# teensy_speeduino_5_1.net
KiCad netlist of a schematic drawn in EAGLE
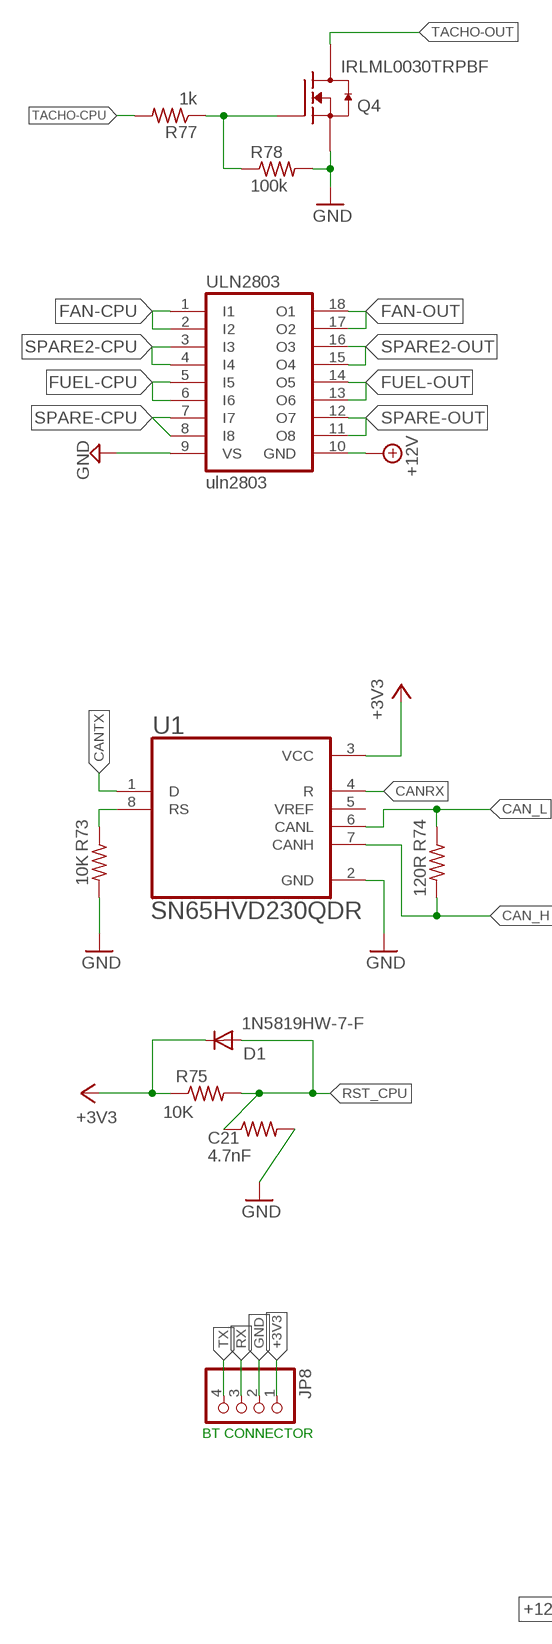
[diagram p0: schematic, sheet 1, part 1 of 2]
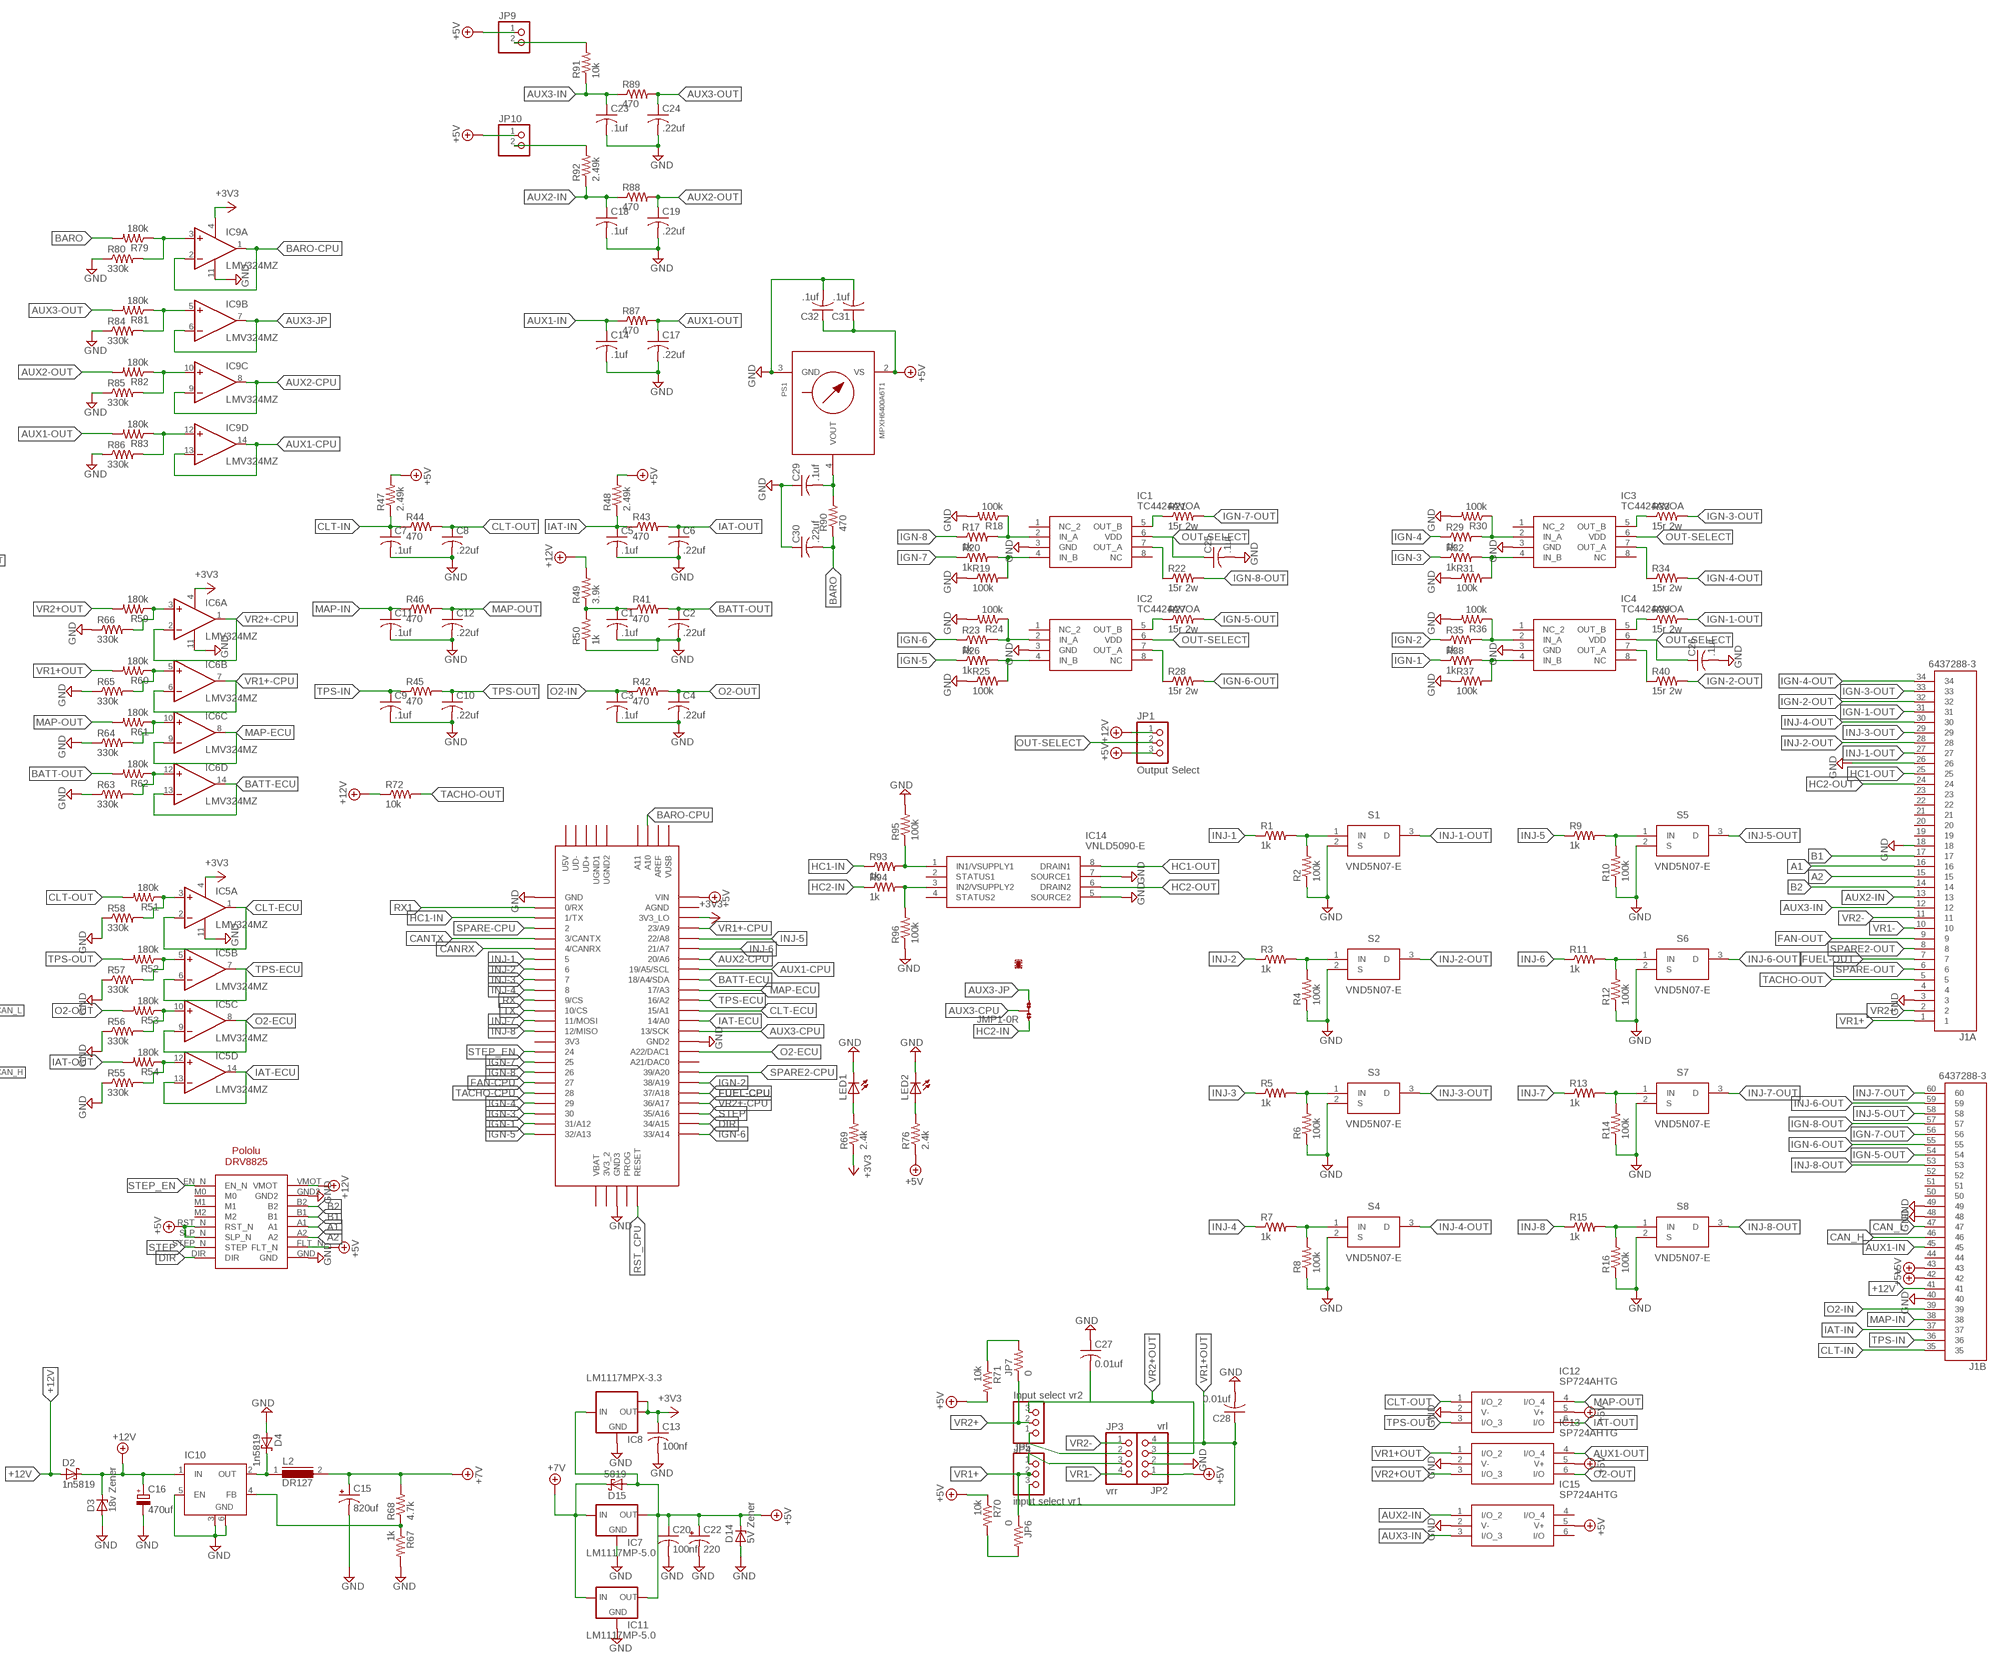
[diagram p1: schematic, sheet 1, part 2 of 2]

(export (version "E")
  (design (tool "Eeschema 10.0.6"))
  (components
    (comp (ref "C1")
      (value ".1uf")
      (footprint "eagle-import:C1206")
      (libsource (lib "eagle-import") (part "C-USC1206"))
    )
    (comp (ref "C2")
      (value ".22uf")
      (footprint "eagle-import:C1206")
      (libsource (lib "eagle-import") (part "C-USC1206"))
    )
    (comp (ref "C3")
      (value ".1uf")
      (footprint "eagle-import:C1206")
      (libsource (lib "eagle-import") (part "C-USC1206"))
    )
    (comp (ref "C4")
      (value ".22uf")
      (footprint "eagle-import:C1206")
      (libsource (lib "eagle-import") (part "C-USC1206"))
    )
    (comp (ref "C5")
      (value ".1uf")
      (footprint "eagle-import:C1206")
      (libsource (lib "eagle-import") (part "C-USC1206"))
    )
    (comp (ref "C6")
      (value ".22uf")
      (footprint "eagle-import:C1206")
      (libsource (lib "eagle-import") (part "C-USC1206"))
    )
    (comp (ref "C7")
      (value ".1uf")
      (footprint "eagle-import:C1206")
      (libsource (lib "eagle-import") (part "C-USC1206"))
    )
    (comp (ref "C8")
      (value ".22uf")
      (footprint "eagle-import:C1206")
      (libsource (lib "eagle-import") (part "C-USC1206"))
    )
    (comp (ref "C9")
      (value ".1uf")
      (footprint "eagle-import:C1206")
      (libsource (lib "eagle-import") (part "C-USC1206"))
    )
    (comp (ref "C10")
      (value ".22uf")
      (footprint "eagle-import:C1206")
      (libsource (lib "eagle-import") (part "C-USC1206"))
    )
    (comp (ref "C11")
      (value ".1uf")
      (footprint "eagle-import:C1206")
      (libsource (lib "eagle-import") (part "C-USC1206"))
    )
    (comp (ref "C12")
      (value ".22uf")
      (footprint "eagle-import:C1206")
      (libsource (lib "eagle-import") (part "C-USC1206"))
    )
    (comp (ref "C13")
      (value "100nf")
      (footprint "eagle-import:C1206")
      (libsource (lib "eagle-import") (part "C-USC1206"))
    )
    (comp (ref "C14")
      (value ".1uf")
      (footprint "eagle-import:C0805")
      (libsource (lib "eagle-import") (part "C-USC0805"))
    )
    (comp (ref "C15")
      (value "820uf")
      (footprint "eagle-import:153CLV-0810")
      (libsource (lib "eagle-import") (part "CPOL-US153CLV-0810"))
    )
    (comp (ref "C16")
      (value "470uf")
      (footprint "eagle-import:153CLV-0810")
      (libsource (lib "eagle-import") (part "CPOL-EU153CLV-0810"))
    )
    (comp (ref "C17")
      (value ".22uf")
      (footprint "eagle-import:C0805")
      (libsource (lib "eagle-import") (part "C-USC0805"))
    )
    (comp (ref "C18")
      (value ".1uf")
      (footprint "eagle-import:C0805")
      (libsource (lib "eagle-import") (part "C-USC0805"))
    )
    (comp (ref "C19")
      (value ".22uf")
      (footprint "eagle-import:C0805")
      (libsource (lib "eagle-import") (part "C-USC0805"))
    )
    (comp (ref "C20")
      (value "100nf")
      (footprint "eagle-import:C1206")
      (libsource (lib "eagle-import") (part "C-USC1206"))
    )
    (comp (ref "C21")
      (value "4.7nF")
      (footprint "eagle-import:R1206")
      (libsource (lib "eagle-import") (part "R-US_R1206"))
    )
    (comp (ref "C22")
      (value "220")
      (footprint "eagle-import:153CLV-0605")
      (libsource (lib "eagle-import") (part "CPOL-US153CLV-0605"))
    )
    (comp (ref "C23")
      (value ".1uf")
      (footprint "eagle-import:C0805")
      (libsource (lib "eagle-import") (part "C-USC0805"))
    )
    (comp (ref "C24")
      (value ".22uf")
      (footprint "eagle-import:C0805")
      (libsource (lib "eagle-import") (part "C-USC0805"))
    )
    (comp (ref "C25")
      (value ".1uf")
      (footprint "eagle-import:C0805")
      (libsource (lib "eagle-import") (part "C-USC0805"))
    )
    (comp (ref "C26")
      (value ".1uf")
      (footprint "eagle-import:C0805")
      (libsource (lib "eagle-import") (part "C-USC0805"))
    )
    (comp (ref "C27")
      (value "0.01uf")
      (footprint "eagle-import:C1206")
      (libsource (lib "eagle-import") (part "C-USC1206"))
    )
    (comp (ref "C28")
      (value "0.01uf")
      (footprint "eagle-import:C1206")
      (libsource (lib "eagle-import") (part "C-USC1206"))
    )
    (comp (ref "C29")
      (value ".1uf")
      (footprint "eagle-import:C1206")
      (libsource (lib "eagle-import") (part "C-USC1206"))
    )
    (comp (ref "C30")
      (value ".22uf")
      (footprint "eagle-import:C1206")
      (libsource (lib "eagle-import") (part "C-USC1206"))
    )
    (comp (ref "C31")
      (value ".1uf")
      (footprint "eagle-import:C1206")
      (libsource (lib "eagle-import") (part "C-USC1206"))
    )
    (comp (ref "C32")
      (value ".1uf")
      (footprint "eagle-import:C1206")
      (libsource (lib "eagle-import") (part "C-USC1206"))
    )
    (comp (ref "D1")
      (value "1N5819HW-7-F")
      (footprint "eagle-import:SOD123")
      (libsource (lib "eagle-import") (part "DIODE-SOD123"))
    )
    (comp (ref "D2")
      (value "1n5819")
      (footprint "eagle-import:SMB")
      (libsource (lib "eagle-import") (part "SCHOTTKY-DIODESMD"))
    )
    (comp (ref "D3")
      (value "18v Zener")
      (footprint "eagle-import:SMB")
      (libsource (lib "eagle-import") (part "ZENER-DIODESMB"))
    )
    (comp (ref "D4")
      (value "1n5819")
      (footprint "eagle-import:SMB")
      (libsource (lib "eagle-import") (part "SCHOTTKY-DIODESMD"))
    )
    (comp (ref "D14")
      (value "5V Zener")
      (footprint "eagle-import:SMB")
      (libsource (lib "eagle-import") (part "ZENER-DIODESMB"))
    )
    (comp (ref "D15")
      (value "5819")
      (footprint "eagle-import:SMB")
      (libsource (lib "eagle-import") (part "SCHOTTKY-DIODESMD"))
    )
    (comp (ref "IC1")
      (value "TC4424AVOA")
      (footprint "eagle-import:SOIC127P600X175-8N")
      (libsource (lib "eagle-import") (part "TC4424AVOA"))
    )
    (comp (ref "IC2")
      (value "TC4424AVOA")
      (footprint "eagle-import:SOIC127P600X175-8N")
      (libsource (lib "eagle-import") (part "TC4424AVOA"))
    )
    (comp (ref "IC3")
      (value "TC4424AVOA")
      (footprint "eagle-import:SOIC127P600X175-8N")
      (libsource (lib "eagle-import") (part "TC4424AVOA"))
    )
    (comp (ref "IC4")
      (value "TC4424AVOA")
      (footprint "eagle-import:SOIC127P600X175-8N")
      (libsource (lib "eagle-import") (part "TC4424AVOA"))
    )
    (comp (ref "IC5")
      (value "LMV324MZ")
      (footprint "eagle-import:TSSOP14")
      (libsource (lib "eagle-import") (part "LMV324?MZ"))
    )
    (comp (ref "IC6")
      (value "LMV324MZ")
      (footprint "eagle-import:TSSOP14")
      (libsource (lib "eagle-import") (part "LMV324?MZ"))
    )
    (comp (ref "IC7")
      (value "LM1117MP-5.0")
      (footprint "eagle-import:SOT223")
      (fields (field (name "MF") "Texas Instruments"))
      (libsource (lib "eagle-import") (part "LM1117?-MP5.0"))
    )
    (comp (ref "IC8")
      (value "LM1117MPX-3.3")
      (footprint "eagle-import:SOT223")
      (libsource (lib "eagle-import") (part "LM1117MPX-3.3"))
    )
    (comp (ref "IC9")
      (value "LMV324MZ")
      (footprint "eagle-import:TSSOP14")
      (libsource (lib "eagle-import") (part "LMV324?MZ"))
    )
    (comp (ref "IC10")
      (value "LM2596S")
      (footprint "eagle-import:TO263-5")
      (libsource (lib "eagle-import") (part "LM2596S"))
    )
    (comp (ref "IC11")
      (value "LM1117MP-5.0")
      (footprint "eagle-import:SOT223")
      (fields (field (name "MF") "Texas Instruments"))
      (libsource (lib "eagle-import") (part "LM1117?-MP5.0"))
    )
    (comp (ref "IC12")
      (value "SP724AHTG")
      (footprint "eagle-import:SOT95P280X145-6N")
      (fields (field (name "RS_PART_NUMBER") "7931982"))
      (libsource (lib "eagle-import") (part "SP724AHTG"))
    )
    (comp (ref "IC13")
      (value "SP724AHTG")
      (footprint "eagle-import:SOT95P280X145-6N")
      (fields (field (name "RS_PART_NUMBER") "7931982"))
      (libsource (lib "eagle-import") (part "SP724AHTG"))
    )
    (comp (ref "IC14")
      (value "VNLD5090-E")
      (footprint "eagle-import:SOIC127P600X175-8N")
      (fields (field (name "MOUSER_PART_NUMBER") "511-VNLD5090-E"))
      (libsource (lib "eagle-import") (part "VNLD5090-E"))
    )
    (comp (ref "IC15")
      (value "SP724AHTG")
      (footprint "eagle-import:SOT95P280X145-6N")
      (fields (field (name "RS_PART_NUMBER") "7931982"))
      (libsource (lib "eagle-import") (part "SP724AHTG"))
    )
    (comp (ref "J1")
      (value "6437288-3")
      (footprint "eagle-import:TE_6437288-3")
      (fields (field (name "DIGI-KEY_PART_NUMBER") "A122211-ND") (field (name "MF") "TE Connectivity"))
      (libsource (lib "eagle-import") (part "6437288-3"))
    )
    (comp (ref "JMP1")
      (value "0R-JUMPA")
      (footprint "eagle-import:A0R-JMP")
      (libsource (lib "eagle-import") (part "0R-JUMPA"))
    )
    (comp (ref "JP1")
      (value "Output Select")
      (footprint "eagle-import:1X03")
      (libsource (lib "eagle-import") (part "PINHD-1X3"))
    )
    (comp (ref "JP2")
      (value "vrl")
      (footprint "eagle-import:1X04")
      (libsource (lib "eagle-import") (part "pinhead_325_PINHD-1X4"))
    )
    (comp (ref "JP3")
      (value "vrr")
      (footprint "eagle-import:1X04")
      (libsource (lib "eagle-import") (part "pinhead_325_PINHD-1X4"))
    )
    (comp (ref "JP4")
      (value "Input select vr2")
      (footprint "eagle-import:1X03")
      (libsource (lib "eagle-import") (part "PINHD-1X3"))
    )
    (comp (ref "JP5")
      (value "input select vr1")
      (footprint "eagle-import:1X03")
      (libsource (lib "eagle-import") (part "PINHD-1X3"))
    )
    (comp (ref "JP6")
      (value "0")
      (footprint "eagle-import:R0805")
      (libsource (lib "eagle-import") (part "R-US_R0805"))
    )
    (comp (ref "JP7")
      (value "0")
      (footprint "eagle-import:R0805")
      (libsource (lib "eagle-import") (part "R-US_R0805"))
    )
    (comp (ref "JP8")
      (value "PINHD-1X4")
      (footprint "eagle-import:1X04")
      (libsource (lib "eagle-import") (part "PINHD-1X4"))
    )
    (comp (ref "JP9")
      (value "PINHD-1X2")
      (footprint "eagle-import:1X02")
      (libsource (lib "eagle-import") (part "PINHD-1X2"))
    )
    (comp (ref "JP10")
      (value "PINHD-1X2")
      (footprint "eagle-import:1X02")
      (libsource (lib "eagle-import") (part "PINHD-1X2"))
    )
    (comp (ref "L2")
      (value "DR127")
      (footprint "eagle-import:DR127")
      (libsource (lib "eagle-import") (part "DR127"))
    )
    (comp (ref "LED1")
      (value "LEDSML1206")
      (footprint "eagle-import:SML1206")
      (libsource (lib "eagle-import") (part "LEDSML1206"))
    )
    (comp (ref "LED2")
      (value "LEDSML1206")
      (footprint "eagle-import:SML1206")
      (libsource (lib "eagle-import") (part "LEDSML1206"))
    )
    (comp (ref "PS1")
      (value "MPXH6400A6T1")
      (footprint "eagle-import:1317")
      (libsource (lib "eagle-import") (part "MPXH6400A6T1"))
    )
    (comp (ref "Q4")
      (value "IRLML0030TRPBF")
      (footprint "eagle-import:SOT95P280X135-3N")
      (libsource (lib "eagle-import") (part "MOSFET-NCH_SOT-23"))
    )
    (comp (ref "R1")
      (value "1k")
      (footprint "eagle-import:R1206")
      (libsource (lib "eagle-import") (part "R-US_R1206"))
    )
    (comp (ref "R2")
      (value "100k")
      (footprint "eagle-import:R1206")
      (libsource (lib "eagle-import") (part "R-US_R1206"))
    )
    (comp (ref "R3")
      (value "1k")
      (footprint "eagle-import:R1206")
      (libsource (lib "eagle-import") (part "R-US_R1206"))
    )
    (comp (ref "R4")
      (value "100k")
      (footprint "eagle-import:R1206")
      (libsource (lib "eagle-import") (part "R-US_R1206"))
    )
    (comp (ref "R5")
      (value "1k")
      (footprint "eagle-import:R1206")
      (libsource (lib "eagle-import") (part "R-US_R1206"))
    )
    (comp (ref "R6")
      (value "100k")
      (footprint "eagle-import:R1206")
      (libsource (lib "eagle-import") (part "R-US_R1206"))
    )
    (comp (ref "R7")
      (value "1k")
      (footprint "eagle-import:R1206")
      (libsource (lib "eagle-import") (part "R-US_R1206"))
    )
    (comp (ref "R8")
      (value "100k")
      (footprint "eagle-import:R1206")
      (libsource (lib "eagle-import") (part "R-US_R1206"))
    )
    (comp (ref "R9")
      (value "1k")
      (footprint "eagle-import:R1206")
      (libsource (lib "eagle-import") (part "R-US_R1206"))
    )
    (comp (ref "R10")
      (value "100k")
      (footprint "eagle-import:R1206")
      (libsource (lib "eagle-import") (part "R-US_R1206"))
    )
    (comp (ref "R11")
      (value "1k")
      (footprint "eagle-import:R1206")
      (libsource (lib "eagle-import") (part "R-US_R1206"))
    )
    (comp (ref "R12")
      (value "100k")
      (footprint "eagle-import:R1206")
      (libsource (lib "eagle-import") (part "R-US_R1206"))
    )
    (comp (ref "R13")
      (value "1k")
      (footprint "eagle-import:R1206")
      (libsource (lib "eagle-import") (part "R-US_R1206"))
    )
    (comp (ref "R14")
      (value "100k")
      (footprint "eagle-import:R1206")
      (libsource (lib "eagle-import") (part "R-US_R1206"))
    )
    (comp (ref "R15")
      (value "1k")
      (footprint "eagle-import:R1206")
      (libsource (lib "eagle-import") (part "R-US_R1206"))
    )
    (comp (ref "R16")
      (value "100k")
      (footprint "eagle-import:R1206")
      (libsource (lib "eagle-import") (part "R-US_R1206"))
    )
    (comp (ref "R17")
      (value "1k")
      (footprint "eagle-import:R1206")
      (libsource (lib "eagle-import") (part "R-US_R1206"))
    )
    (comp (ref "R18")
      (value "100k")
      (footprint "eagle-import:R1206")
      (libsource (lib "eagle-import") (part "R-US_R1206"))
    )
    (comp (ref "R19")
      (value "100k")
      (footprint "eagle-import:R1206")
      (libsource (lib "eagle-import") (part "R-US_R1206"))
    )
    (comp (ref "R20")
      (value "1k")
      (footprint "eagle-import:R1206")
      (libsource (lib "eagle-import") (part "R-US_R1206"))
    )
    (comp (ref "R21")
      (value "15r 2w")
      (footprint "eagle-import:R2512")
      (libsource (lib "eagle-import") (part "R-US_R2512"))
    )
    (comp (ref "R22")
      (value "15r 2w")
      (footprint "eagle-import:R2512")
      (libsource (lib "eagle-import") (part "R-US_R2512"))
    )
    (comp (ref "R23")
      (value "1k")
      (footprint "eagle-import:R1206")
      (libsource (lib "eagle-import") (part "R-US_R1206"))
    )
    (comp (ref "R24")
      (value "100k")
      (footprint "eagle-import:R1206")
      (libsource (lib "eagle-import") (part "R-US_R1206"))
    )
    (comp (ref "R25")
      (value "100k")
      (footprint "eagle-import:R1206")
      (libsource (lib "eagle-import") (part "R-US_R1206"))
    )
    (comp (ref "R26")
      (value "1k")
      (footprint "eagle-import:R1206")
      (libsource (lib "eagle-import") (part "R-US_R1206"))
    )
    (comp (ref "R27")
      (value "15r 2w")
      (footprint "eagle-import:R2512")
      (libsource (lib "eagle-import") (part "R-US_R2512"))
    )
    (comp (ref "R28")
      (value "15r 2w")
      (footprint "eagle-import:R2512")
      (libsource (lib "eagle-import") (part "R-US_R2512"))
    )
    (comp (ref "R29")
      (value "1k")
      (footprint "eagle-import:R1206")
      (libsource (lib "eagle-import") (part "R-US_R1206"))
    )
    (comp (ref "R30")
      (value "100k")
      (footprint "eagle-import:R1206")
      (libsource (lib "eagle-import") (part "R-US_R1206"))
    )
    (comp (ref "R31")
      (value "100k")
      (footprint "eagle-import:R1206")
      (libsource (lib "eagle-import") (part "R-US_R1206"))
    )
    (comp (ref "R32")
      (value "1k")
      (footprint "eagle-import:R1206")
      (libsource (lib "eagle-import") (part "R-US_R1206"))
    )
    (comp (ref "R33")
      (value "15r 2w")
      (footprint "eagle-import:R2512")
      (libsource (lib "eagle-import") (part "R-US_R2512"))
    )
    (comp (ref "R34")
      (value "15r 2w")
      (footprint "eagle-import:R2512")
      (libsource (lib "eagle-import") (part "R-US_R2512"))
    )
    (comp (ref "R35")
      (value "1k")
      (footprint "eagle-import:R1206")
      (libsource (lib "eagle-import") (part "R-US_R1206"))
    )
    (comp (ref "R36")
      (value "100k")
      (footprint "eagle-import:R1206")
      (libsource (lib "eagle-import") (part "R-US_R1206"))
    )
    (comp (ref "R37")
      (value "100k")
      (footprint "eagle-import:R1206")
      (libsource (lib "eagle-import") (part "R-US_R1206"))
    )
    (comp (ref "R38")
      (value "1k")
      (footprint "eagle-import:R1206")
      (libsource (lib "eagle-import") (part "R-US_R1206"))
    )
    (comp (ref "R39")
      (value "15r 2w")
      (footprint "eagle-import:R2512")
      (libsource (lib "eagle-import") (part "R-US_R2512"))
    )
    (comp (ref "R40")
      (value "15r 2w")
      (footprint "eagle-import:R2512")
      (libsource (lib "eagle-import") (part "R-US_R2512"))
    )
    (comp (ref "R41")
      (value "470")
      (footprint "eagle-import:R1206")
      (libsource (lib "eagle-import") (part "R-US_R1206"))
    )
    (comp (ref "R42")
      (value "470")
      (footprint "eagle-import:R1206")
      (libsource (lib "eagle-import") (part "R-US_R1206"))
    )
    (comp (ref "R43")
      (value "470")
      (footprint "eagle-import:R1206")
      (libsource (lib "eagle-import") (part "R-US_R1206"))
    )
    (comp (ref "R44")
      (value "470")
      (footprint "eagle-import:R1206")
      (libsource (lib "eagle-import") (part "R-US_R1206"))
    )
    (comp (ref "R45")
      (value "470")
      (footprint "eagle-import:R1206")
      (libsource (lib "eagle-import") (part "R-US_R1206"))
    )
    (comp (ref "R46")
      (value "470")
      (footprint "eagle-import:R1206")
      (libsource (lib "eagle-import") (part "R-US_R1206"))
    )
    (comp (ref "R47")
      (value "2.49k")
      (footprint "eagle-import:R1206")
      (libsource (lib "eagle-import") (part "R-US_R1206"))
    )
    (comp (ref "R48")
      (value "2.49k")
      (footprint "eagle-import:R1206")
      (libsource (lib "eagle-import") (part "R-US_R1206"))
    )
    (comp (ref "R49")
      (value "3.9k")
      (footprint "eagle-import:R1206")
      (libsource (lib "eagle-import") (part "R-US_R1206"))
    )
    (comp (ref "R50")
      (value "1k")
      (footprint "eagle-import:R1206")
      (libsource (lib "eagle-import") (part "R-US_R1206"))
    )
    (comp (ref "R51")
      (value "180k")
      (footprint "eagle-import:R1206")
      (libsource (lib "eagle-import") (part "R-US_R1206"))
    )
    (comp (ref "R52")
      (value "180k")
      (footprint "eagle-import:R1206")
      (libsource (lib "eagle-import") (part "R-US_R1206"))
    )
    (comp (ref "R53")
      (value "180k")
      (footprint "eagle-import:R1206")
      (libsource (lib "eagle-import") (part "R-US_R1206"))
    )
    (comp (ref "R54")
      (value "180k")
      (footprint "eagle-import:R1206")
      (libsource (lib "eagle-import") (part "R-US_R1206"))
    )
    (comp (ref "R55")
      (value "330k")
      (footprint "eagle-import:R1206")
      (libsource (lib "eagle-import") (part "R-US_R1206"))
    )
    (comp (ref "R56")
      (value "330k")
      (footprint "eagle-import:R1206")
      (libsource (lib "eagle-import") (part "R-US_R1206"))
    )
    (comp (ref "R57")
      (value "330k")
      (footprint "eagle-import:R1206")
      (libsource (lib "eagle-import") (part "R-US_R1206"))
    )
    (comp (ref "R58")
      (value "330k")
      (footprint "eagle-import:R1206")
      (libsource (lib "eagle-import") (part "R-US_R1206"))
    )
    (comp (ref "R59")
      (value "180k")
      (footprint "eagle-import:R1206")
      (libsource (lib "eagle-import") (part "R-US_R1206"))
    )
    (comp (ref "R60")
      (value "180k")
      (footprint "eagle-import:R1206")
      (libsource (lib "eagle-import") (part "R-US_R1206"))
    )
    (comp (ref "R61")
      (value "180k")
      (footprint "eagle-import:R1206")
      (libsource (lib "eagle-import") (part "R-US_R1206"))
    )
    (comp (ref "R62")
      (value "180k")
      (footprint "eagle-import:R1206")
      (libsource (lib "eagle-import") (part "R-US_R1206"))
    )
    (comp (ref "R63")
      (value "330k")
      (footprint "eagle-import:R1206")
      (libsource (lib "eagle-import") (part "R-US_R1206"))
    )
    (comp (ref "R64")
      (value "330k")
      (footprint "eagle-import:R1206")
      (libsource (lib "eagle-import") (part "R-US_R1206"))
    )
    (comp (ref "R65")
      (value "330k")
      (footprint "eagle-import:R1206")
      (libsource (lib "eagle-import") (part "R-US_R1206"))
    )
    (comp (ref "R66")
      (value "330k")
      (footprint "eagle-import:R1206")
      (libsource (lib "eagle-import") (part "R-US_R1206"))
    )
    (comp (ref "R67")
      (value "1k")
      (footprint "eagle-import:R1206")
      (libsource (lib "eagle-import") (part "R-US_R1206"))
    )
    (comp (ref "R68")
      (value "4.7k")
      (footprint "eagle-import:R1206")
      (libsource (lib "eagle-import") (part "R-US_R1206"))
    )
    (comp (ref "R69")
      (value "2.4k")
      (footprint "eagle-import:R1206")
      (libsource (lib "eagle-import") (part "R-US_R1206"))
    )
    (comp (ref "R70")
      (value "10k")
      (footprint "eagle-import:R1206")
      (libsource (lib "eagle-import") (part "R-US_R1206"))
    )
    (comp (ref "R71")
      (value "10k")
      (footprint "eagle-import:R1206")
      (libsource (lib "eagle-import") (part "R-US_R1206"))
    )
    (comp (ref "R72")
      (value "10k")
      (footprint "eagle-import:R1206")
      (libsource (lib "eagle-import") (part "R-US_R1206"))
    )
    (comp (ref "R73")
      (value "10K")
      (footprint "eagle-import:R1206")
      (libsource (lib "eagle-import") (part "R-US_R1206"))
    )
    (comp (ref "R74")
      (value "120R")
      (footprint "eagle-import:R1206")
      (libsource (lib "eagle-import") (part "R-US_R1206"))
    )
    (comp (ref "R75")
      (value "10K")
      (footprint "eagle-import:R1206")
      (libsource (lib "eagle-import") (part "R-US_R1206"))
    )
    (comp (ref "R76")
      (value "2.4k")
      (footprint "eagle-import:R1206")
      (libsource (lib "eagle-import") (part "R-US_R1206"))
    )
    (comp (ref "R77")
      (value "1k")
      (footprint "eagle-import:R1206")
      (libsource (lib "eagle-import") (part "R-US_R1206"))
    )
    (comp (ref "R78")
      (value "100k")
      (footprint "eagle-import:R1206")
      (libsource (lib "eagle-import") (part "R-US_R1206"))
    )
    (comp (ref "R79")
      (value "180k")
      (footprint "eagle-import:R0805")
      (libsource (lib "eagle-import") (part "R-US_R0805"))
    )
    (comp (ref "R80")
      (value "330k")
      (footprint "eagle-import:R0805")
      (libsource (lib "eagle-import") (part "R-US_R0805"))
    )
    (comp (ref "R81")
      (value "180k")
      (footprint "eagle-import:R0805")
      (libsource (lib "eagle-import") (part "R-US_R0805"))
    )
    (comp (ref "R82")
      (value "180k")
      (footprint "eagle-import:R0805")
      (libsource (lib "eagle-import") (part "R-US_R0805"))
    )
    (comp (ref "R83")
      (value "180k")
      (footprint "eagle-import:R0805")
      (libsource (lib "eagle-import") (part "R-US_R0805"))
    )
    (comp (ref "R84")
      (value "330k")
      (footprint "eagle-import:R0805")
      (libsource (lib "eagle-import") (part "R-US_R0805"))
    )
    (comp (ref "R85")
      (value "330k")
      (footprint "eagle-import:R0805")
      (libsource (lib "eagle-import") (part "R-US_R0805"))
    )
    (comp (ref "R86")
      (value "330k")
      (footprint "eagle-import:R0805")
      (libsource (lib "eagle-import") (part "R-US_R0805"))
    )
    (comp (ref "R87")
      (value "470")
      (footprint "eagle-import:R0805")
      (libsource (lib "eagle-import") (part "R-US_R0805"))
    )
    (comp (ref "R88")
      (value "470")
      (footprint "eagle-import:R0805")
      (libsource (lib "eagle-import") (part "R-US_R0805"))
    )
    (comp (ref "R89")
      (value "470")
      (footprint "eagle-import:R0805")
      (libsource (lib "eagle-import") (part "R-US_R0805"))
    )
    (comp (ref "R90")
      (value "470")
      (footprint "eagle-import:R1206")
      (libsource (lib "eagle-import") (part "R-US_R1206"))
    )
    (comp (ref "R91")
      (value "10k")
      (footprint "eagle-import:R1206")
      (libsource (lib "eagle-import") (part "R-US_R1206"))
    )
    (comp (ref "R92")
      (value "2.49k")
      (footprint "eagle-import:R1206")
      (libsource (lib "eagle-import") (part "R-US_R1206"))
    )
    (comp (ref "R93")
      (value "1k")
      (footprint "eagle-import:R1206")
      (libsource (lib "eagle-import") (part "R-US_R1206"))
    )
    (comp (ref "R94")
      (value "1k")
      (footprint "eagle-import:R1206")
      (libsource (lib "eagle-import") (part "R-US_R1206"))
    )
    (comp (ref "R95")
      (value "100k")
      (footprint "eagle-import:R1206")
      (libsource (lib "eagle-import") (part "R-US_R1206"))
    )
    (comp (ref "R96")
      (value "100k")
      (footprint "eagle-import:R1206")
      (libsource (lib "eagle-import") (part "R-US_R1206"))
    )
    (comp (ref "S1")
      (value "VND5N07-E")
      (footprint "eagle-import:TO-252-(DPAK)_1")
      (fields (field (name "RS_PART_NUMBER") "3511351"))
      (libsource (lib "eagle-import") (part "VND5N07-E"))
    )
    (comp (ref "S2")
      (value "VND5N07-E")
      (footprint "eagle-import:TO-252-(DPAK)_1")
      (fields (field (name "RS_PART_NUMBER") "3511351"))
      (libsource (lib "eagle-import") (part "VND5N07-E"))
    )
    (comp (ref "S3")
      (value "VND5N07-E")
      (footprint "eagle-import:TO-252-(DPAK)_1")
      (fields (field (name "RS_PART_NUMBER") "3511351"))
      (libsource (lib "eagle-import") (part "VND5N07-E"))
    )
    (comp (ref "S4")
      (value "VND5N07-E")
      (footprint "eagle-import:TO-252-(DPAK)_1")
      (fields (field (name "RS_PART_NUMBER") "3511351"))
      (libsource (lib "eagle-import") (part "VND5N07-E"))
    )
    (comp (ref "S5")
      (value "VND5N07-E")
      (footprint "eagle-import:TO-252-(DPAK)_1")
      (fields (field (name "RS_PART_NUMBER") "3511351"))
      (libsource (lib "eagle-import") (part "VND5N07-E"))
    )
    (comp (ref "S6")
      (value "VND5N07-E")
      (footprint "eagle-import:TO-252-(DPAK)_1")
      (fields (field (name "RS_PART_NUMBER") "3511351"))
      (libsource (lib "eagle-import") (part "VND5N07-E"))
    )
    (comp (ref "S7")
      (value "VND5N07-E")
      (footprint "eagle-import:TO-252-(DPAK)_1")
      (fields (field (name "RS_PART_NUMBER") "3511351"))
      (libsource (lib "eagle-import") (part "VND5N07-E"))
    )
    (comp (ref "S8")
      (value "VND5N07-E")
      (footprint "eagle-import:TO-252-(DPAK)_1")
      (fields (field (name "RS_PART_NUMBER") "3511351"))
      (libsource (lib "eagle-import") (part "VND5N07-E"))
    )
    (comp (ref "U$1")
      (value "TEENSY_3.5/3.6")
      (footprint "eagle-import:TEENSY_3.5_3.6")
      (libsource (lib "eagle-import") (part "TEENSY_3.5/3.6"))
    )
    (comp (ref "U$3")
      (value "POLOLU-DRV8825")
      (footprint "eagle-import:POLOLU-DRV8825")
      (libsource (lib "eagle-import") (part "POLOLU-DRV8825"))
    )
    (comp (ref "U1")
      (value "SN65HVD230QDR")
      (footprint "eagle-import:SOIC127P600X175-8N")
      (fields (field (name "MF") "Texas Instruments"))
      (libsource (lib "eagle-import") (part "SN65HVD230QDR"))
    )
    (comp (ref "ULN2803")
      (value "uln2803")
      (footprint "eagle-import:SO18W")
      (libsource (lib "eagle-import") (part "UDN298LW4"))
    )
  )
  (nets
    (net (code "1") (name "+3V3") (class "Default")
      (node (ref "C13") (pin "1") (pinfunction "1_1") (pintype "passive"))
      (node (ref "D1") (pin "C") (pinfunction "C_C") (pintype "passive"))
      (node (ref "IC5") (pin "4") (pinfunction "V+_4") (pintype "power_in"))
      (node (ref "IC6") (pin "4") (pinfunction "V+_4") (pintype "power_in"))
      (node (ref "IC8") (pin "2") (pinfunction "OUT_2") (pintype "passive"))
      (node (ref "IC8") (pin "TAB") (pinfunction "OUT1_TAB") (pintype "passive"))
      (node (ref "IC9") (pin "4") (pinfunction "V+_4") (pintype "power_in"))
      (node (ref "JP8") (pin "1") (pinfunction "1_1") (pintype "passive"))
      (node (ref "R69") (pin "1") (pinfunction "1_1") (pintype "passive"))
      (node (ref "R75") (pin "1") (pinfunction "1_1") (pintype "passive"))
      (node (ref "U$1") (pin "3V3_LO") (pinfunction "3V3_LO_3V3_LO") (pintype "bidirectional"))
      (node (ref "U1") (pin "3") (pinfunction "VCC_3") (pintype "power_in"))
    )
    (net (code "2") (name "+5V") (class "Default")
      (node (ref "C20") (pin "1") (pinfunction "1_1") (pintype "passive"))
      (node (ref "C22") (pin "+") (pinfunction "+_+") (pintype "passive"))
      (node (ref "C31") (pin "1") (pinfunction "1_1") (pintype "passive"))
      (node (ref "C32") (pin "1") (pinfunction "1_1") (pintype "passive"))
      (node (ref "D14") (pin "C") (pinfunction "C_C") (pintype "passive"))
      (node (ref "D15") (pin "A") (pinfunction "A_A") (pintype "passive"))
      (node (ref "IC11") (pin "2") (pinfunction "OUT_2") (pintype "passive"))
      (node (ref "IC11") (pin "4") (pinfunction "OUT_4") (pintype "passive"))
      (node (ref "IC12") (pin "5") (pinfunction "V+_5") (pintype "bidirectional"))
      (node (ref "IC13") (pin "5") (pinfunction "V+_5") (pintype "bidirectional"))
      (node (ref "IC15") (pin "5") (pinfunction "V+_5") (pintype "bidirectional"))
      (node (ref "IC7") (pin "2") (pinfunction "OUT_2") (pintype "passive"))
      (node (ref "IC7") (pin "4") (pinfunction "OUT_4") (pintype "passive"))
      (node (ref "IC8") (pin "3") (pinfunction "IN_3") (pintype "input"))
      (node (ref "J1") (pin "42") (pinfunction "42_42") (pintype "passive"))
      (node (ref "J1") (pin "43") (pinfunction "43_43") (pintype "passive"))
      (node (ref "JP1") (pin "3") (pinfunction "3_3") (pintype "passive"))
      (node (ref "JP10") (pin "1") (pinfunction "1_1") (pintype "passive"))
      (node (ref "JP2") (pin "1") (pinfunction "1_1") (pintype "passive"))
      (node (ref "JP9") (pin "1") (pinfunction "1_1") (pintype "passive"))
      (node (ref "PS1") (pin "2") (pinfunction "VS_2") (pintype "power_in"))
      (node (ref "R47") (pin "2") (pinfunction "2_2") (pintype "passive"))
      (node (ref "R48") (pin "2") (pinfunction "2_2") (pintype "passive"))
      (node (ref "R70") (pin "1") (pinfunction "1_1") (pintype "passive"))
      (node (ref "R71") (pin "2") (pinfunction "2_2") (pintype "passive"))
      (node (ref "R76") (pin "1") (pinfunction "1_1") (pintype "passive"))
      (node (ref "U$1") (pin "VIN") (pinfunction "VIN_VIN") (pintype "bidirectional"))
      (node (ref "U$3") (pin "FLT_N") (pinfunction "FLT_N_FLT_N") (pintype "bidirectional"))
      (node (ref "U$3") (pin "RST_N") (pinfunction "RST_N_RST_N") (pintype "bidirectional"))
      (node (ref "U$3") (pin "SLP_N") (pinfunction "SLP_N_SLP_N") (pintype "bidirectional"))
    )
    (net (code "3") (name "+7V") (class "Default")
      (node (ref "C15") (pin "+") (pinfunction "+_+") (pintype "passive"))
      (node (ref "D15") (pin "C") (pinfunction "C_C") (pintype "passive"))
      (node (ref "IC11") (pin "3") (pinfunction "IN_3") (pintype "input"))
      (node (ref "IC7") (pin "3") (pinfunction "IN_3") (pintype "input"))
      (node (ref "L2") (pin "2") (pinfunction "2_2") (pintype "passive"))
      (node (ref "R68") (pin "2") (pinfunction "2_2") (pintype "passive"))
    )
    (net (code "4") (name "+12V") (class "Default")
      (node (ref "C16") (pin "+") (pinfunction "+_+") (pintype "passive"))
      (node (ref "D2") (pin "A") (pinfunction "A_A") (pintype "passive"))
      (node (ref "D2") (pin "C") (pinfunction "C_C") (pintype "passive"))
      (node (ref "D3") (pin "C") (pinfunction "C_C") (pintype "passive"))
      (node (ref "IC10") (pin "1") (pinfunction "IN_1") (pintype "input"))
      (node (ref "J1") (pin "41") (pinfunction "41_41") (pintype "passive"))
      (node (ref "JP1") (pin "1") (pinfunction "1_1") (pintype "passive"))
      (node (ref "R49") (pin "2") (pinfunction "2_2") (pintype "passive"))
      (node (ref "R72") (pin "1") (pinfunction "1_1") (pintype "passive"))
      (node (ref "U$3") (pin "VMOT") (pinfunction "VMOT_VMOT") (pintype "bidirectional"))
      (node (ref "ULN2803") (pin "10") (pinfunction "GND_10") (pintype "power_in"))
    )
    (net (code "5") (name "A1") (class "Default")
      (node (ref "J1") (pin "16") (pinfunction "16_16") (pintype "passive"))
      (node (ref "U$3") (pin "A1") (pinfunction "A1_A1") (pintype "bidirectional"))
    )
    (net (code "6") (name "A2") (class "Default")
      (node (ref "J1") (pin "15") (pinfunction "15_15") (pintype "passive"))
      (node (ref "U$3") (pin "A2") (pinfunction "A2_A2") (pintype "bidirectional"))
    )
    (net (code "7") (name "AUX1-CPU") (class "Default")
      (node (ref "IC9") (pin "13") (pinfunction "-IN_13") (pintype "input"))
      (node (ref "IC9") (pin "14") (pinfunction "OUT_14") (pintype "output"))
      (node (ref "U$1") (pin "19/A5/SCL") (pinfunction "19/A5/SCL_19/A5/SCL") (pintype "bidirectional"))
    )
    (net (code "8") (name "AUX1-IN") (class "Default")
      (node (ref "C14") (pin "1") (pinfunction "1_1") (pintype "passive"))
      (node (ref "J1") (pin "45") (pinfunction "45_45") (pintype "passive"))
      (node (ref "R87") (pin "1") (pinfunction "1_1") (pintype "passive"))
    )
    (net (code "9") (name "AUX1-OUT") (class "Default")
      (node (ref "C17") (pin "1") (pinfunction "1_1") (pintype "passive"))
      (node (ref "IC13") (pin "4") (pinfunction "I/O_4_4") (pintype "bidirectional"))
      (node (ref "R83") (pin "2") (pinfunction "2_2") (pintype "passive"))
      (node (ref "R87") (pin "2") (pinfunction "2_2") (pintype "passive"))
    )
    (net (code "10") (name "AUX2-CPU") (class "Default")
      (node (ref "IC9") (pin "8") (pinfunction "OUT_8") (pintype "output"))
      (node (ref "IC9") (pin "9") (pinfunction "-IN_9") (pintype "input"))
      (node (ref "U$1") (pin "20/A6") (pinfunction "20/A6_20/A6") (pintype "bidirectional"))
    )
    (net (code "11") (name "AUX2-IN") (class "Default")
      (node (ref "C18") (pin "1") (pinfunction "1_1") (pintype "passive"))
      (node (ref "IC15") (pin "1") (pinfunction "I/O_2_1") (pintype "bidirectional"))
      (node (ref "J1") (pin "13") (pinfunction "13_13") (pintype "passive"))
      (node (ref "R88") (pin "1") (pinfunction "1_1") (pintype "passive"))
      (node (ref "R92") (pin "1") (pinfunction "1_1") (pintype "passive"))
    )
    (net (code "12") (name "AUX2-OUT") (class "Default")
      (node (ref "C19") (pin "1") (pinfunction "1_1") (pintype "passive"))
      (node (ref "R82") (pin "2") (pinfunction "2_2") (pintype "passive"))
      (node (ref "R88") (pin "2") (pinfunction "2_2") (pintype "passive"))
    )
    (net (code "13") (name "AUX3-CPU") (class "Default")
      (node (ref "JMP1") (pin "2") (pinfunction "2_2") (pintype "passive"))
      (node (ref "U$1") (pin "13/SCK") (pinfunction "13/SCK_13/SCK") (pintype "bidirectional"))
    )
    (net (code "14") (name "AUX3-IN") (class "Default")
      (node (ref "C23") (pin "1") (pinfunction "1_1") (pintype "passive"))
      (node (ref "IC15") (pin "3") (pinfunction "I/O_3_3") (pintype "bidirectional"))
      (node (ref "J1") (pin "12") (pinfunction "12_12") (pintype "passive"))
      (node (ref "R89") (pin "1") (pinfunction "1_1") (pintype "passive"))
      (node (ref "R91") (pin "1") (pinfunction "1_1") (pintype "passive"))
    )
    (net (code "15") (name "AUX3-JP") (class "Default")
      (node (ref "IC9") (pin "6") (pinfunction "-IN_6") (pintype "input"))
      (node (ref "IC9") (pin "7") (pinfunction "OUT_7") (pintype "output"))
      (node (ref "JMP1") (pin "3") (pinfunction "3_3") (pintype "passive"))
    )
    (net (code "16") (name "AUX3-OUT") (class "Default")
      (node (ref "C24") (pin "1") (pinfunction "1_1") (pintype "passive"))
      (node (ref "R81") (pin "2") (pinfunction "2_2") (pintype "passive"))
      (node (ref "R89") (pin "2") (pinfunction "2_2") (pintype "passive"))
    )
    (net (code "17") (name "B1") (class "Default")
      (node (ref "J1") (pin "17") (pinfunction "17_17") (pintype "passive"))
      (node (ref "U$3") (pin "B1") (pinfunction "B1_B1") (pintype "bidirectional"))
    )
    (net (code "18") (name "B2") (class "Default")
      (node (ref "J1") (pin "14") (pinfunction "14_14") (pintype "passive"))
      (node (ref "U$3") (pin "B2") (pinfunction "B2_B2") (pintype "bidirectional"))
    )
    (net (code "19") (name "BARO") (class "Default")
      (node (ref "C30") (pin "2") (pinfunction "2_2") (pintype "passive"))
      (node (ref "R79") (pin "2") (pinfunction "2_2") (pintype "passive"))
      (node (ref "R90") (pin "1") (pinfunction "1_1") (pintype "passive"))
    )
    (net (code "20") (name "BARO-CPU") (class "Default")
      (node (ref "IC9") (pin "1") (pinfunction "OUT_1") (pintype "output"))
      (node (ref "IC9") (pin "2") (pinfunction "-IN_2") (pintype "input"))
      (node (ref "U$1") (pin "A10") (pinfunction "A10_A10") (pintype "bidirectional"))
    )
    (net (code "21") (name "BATT-ECU") (class "Default")
      (node (ref "IC6") (pin "13") (pinfunction "-IN_13") (pintype "input"))
      (node (ref "IC6") (pin "14") (pinfunction "OUT_14") (pintype "output"))
      (node (ref "U$1") (pin "18/A4/SDA") (pinfunction "18/A4/SDA_18/A4/SDA") (pintype "bidirectional"))
    )
    (net (code "22") (name "BATT-OUT") (class "Default")
      (node (ref "C2") (pin "1") (pinfunction "1_1") (pintype "passive"))
      (node (ref "R41") (pin "2") (pinfunction "2_2") (pintype "passive"))
      (node (ref "R62") (pin "2") (pinfunction "2_2") (pintype "passive"))
    )
    (net (code "23") (name "CANRX") (class "Default")
      (node (ref "U$1") (pin "4/CANRX") (pinfunction "4/CANRX_4/CANRX") (pintype "bidirectional"))
      (node (ref "U1") (pin "4") (pinfunction "R_4") (pintype "output"))
    )
    (net (code "24") (name "CANTX") (class "Default")
      (node (ref "U$1") (pin "3/CANTX") (pinfunction "3/CANTX_3/CANTX") (pintype "bidirectional"))
      (node (ref "U1") (pin "1") (pinfunction "D_1") (pintype "input"))
    )
    (net (code "25") (name "CAN_H") (class "Default")
      (node (ref "J1") (pin "46") (pinfunction "46_46") (pintype "passive"))
      (node (ref "R74") (pin "2") (pinfunction "2_2") (pintype "passive"))
      (node (ref "U1") (pin "7") (pinfunction "CANH_7") (pintype "output"))
    )
    (net (code "26") (name "CAN_L") (class "Default")
      (node (ref "J1") (pin "47") (pinfunction "47_47") (pintype "passive"))
      (node (ref "R74") (pin "1") (pinfunction "1_1") (pintype "passive"))
      (node (ref "U1") (pin "6") (pinfunction "CANL_6") (pintype "output"))
    )
    (net (code "27") (name "CLT-ECU") (class "Default")
      (node (ref "IC5") (pin "1") (pinfunction "OUT_1") (pintype "output"))
      (node (ref "IC5") (pin "2") (pinfunction "-IN_2") (pintype "input"))
      (node (ref "U$1") (pin "15/A1") (pinfunction "15/A1_15/A1") (pintype "bidirectional"))
    )
    (net (code "28") (name "CLT-IN") (class "Default")
      (node (ref "C7") (pin "1") (pinfunction "1_1") (pintype "passive"))
      (node (ref "J1") (pin "35") (pinfunction "35_35") (pintype "passive"))
      (node (ref "R44") (pin "1") (pinfunction "1_1") (pintype "passive"))
      (node (ref "R47") (pin "1") (pinfunction "1_1") (pintype "passive"))
    )
    (net (code "29") (name "CLT-OUT") (class "Default")
      (node (ref "C8") (pin "1") (pinfunction "1_1") (pintype "passive"))
      (node (ref "IC12") (pin "1") (pinfunction "I/O_2_1") (pintype "bidirectional"))
      (node (ref "R44") (pin "2") (pinfunction "2_2") (pintype "passive"))
      (node (ref "R51") (pin "2") (pinfunction "2_2") (pintype "passive"))
    )
    (net (code "30") (name "DIR") (class "Default")
      (node (ref "U$1") (pin "34/A15") (pinfunction "34/A15_34/A15") (pintype "bidirectional"))
      (node (ref "U$3") (pin "DIR") (pinfunction "DIR_DIR") (pintype "bidirectional"))
    )
    (net (code "31") (name "FAN-CPU") (class "Default")
      (node (ref "U$1") (pin "27") (pinfunction "27_27") (pintype "bidirectional"))
      (node (ref "ULN2803") (pin "1") (pinfunction "I1_1") (pintype "input"))
      (node (ref "ULN2803") (pin "2") (pinfunction "I2_2") (pintype "input"))
    )
    (net (code "32") (name "FAN-OUT") (class "Default")
      (node (ref "J1") (pin "9") (pinfunction "9_9") (pintype "passive"))
      (node (ref "ULN2803") (pin "17") (pinfunction "O2_17") (pintype "open_collector"))
      (node (ref "ULN2803") (pin "18") (pinfunction "O1_18") (pintype "open_collector"))
    )
    (net (code "33") (name "FUEL-CPU") (class "Default")
      (node (ref "U$1") (pin "37/A18") (pinfunction "37/A18_37/A18") (pintype "bidirectional"))
      (node (ref "ULN2803") (pin "5") (pinfunction "I5_5") (pintype "input"))
      (node (ref "ULN2803") (pin "6") (pinfunction "I6_6") (pintype "input"))
    )
    (net (code "34") (name "FUEL-OUT") (class "Default")
      (node (ref "J1") (pin "7") (pinfunction "7_7") (pintype "passive"))
      (node (ref "ULN2803") (pin "13") (pinfunction "O6_13") (pintype "open_collector"))
      (node (ref "ULN2803") (pin "14") (pinfunction "O5_14") (pintype "open_collector"))
    )
    (net (code "35") (name "GND") (class "Default")
      (node (ref "C1") (pin "2") (pinfunction "2_2") (pintype "passive"))
      (node (ref "C10") (pin "2") (pinfunction "2_2") (pintype "passive"))
      (node (ref "C11") (pin "2") (pinfunction "2_2") (pintype "passive"))
      (node (ref "C12") (pin "2") (pinfunction "2_2") (pintype "passive"))
      (node (ref "C13") (pin "2") (pinfunction "2_2") (pintype "passive"))
      (node (ref "C14") (pin "2") (pinfunction "2_2") (pintype "passive"))
      (node (ref "C15") (pin "-") (pinfunction "-_-") (pintype "passive"))
      (node (ref "C16") (pin "-") (pinfunction "-_-") (pintype "passive"))
      (node (ref "C17") (pin "2") (pinfunction "2_2") (pintype "passive"))
      (node (ref "C18") (pin "2") (pinfunction "2_2") (pintype "passive"))
      (node (ref "C19") (pin "2") (pinfunction "2_2") (pintype "passive"))
      (node (ref "C2") (pin "2") (pinfunction "2_2") (pintype "passive"))
      (node (ref "C20") (pin "2") (pinfunction "2_2") (pintype "passive"))
      (node (ref "C21") (pin "2") (pinfunction "2_2") (pintype "passive"))
      (node (ref "C22") (pin "-") (pinfunction "-_-") (pintype "passive"))
      (node (ref "C23") (pin "2") (pinfunction "2_2") (pintype "passive"))
      (node (ref "C24") (pin "2") (pinfunction "2_2") (pintype "passive"))
      (node (ref "C25") (pin "2") (pinfunction "2_2") (pintype "passive"))
      (node (ref "C26") (pin "2") (pinfunction "2_2") (pintype "passive"))
      (node (ref "C27") (pin "1") (pinfunction "1_1") (pintype "passive"))
      (node (ref "C28") (pin "2") (pinfunction "2_2") (pintype "passive"))
      (node (ref "C29") (pin "1") (pinfunction "1_1") (pintype "passive"))
      (node (ref "C3") (pin "2") (pinfunction "2_2") (pintype "passive"))
      (node (ref "C30") (pin "1") (pinfunction "1_1") (pintype "passive"))
      (node (ref "C31") (pin "2") (pinfunction "2_2") (pintype "passive"))
      (node (ref "C32") (pin "2") (pinfunction "2_2") (pintype "passive"))
      (node (ref "C4") (pin "2") (pinfunction "2_2") (pintype "passive"))
      (node (ref "C5") (pin "2") (pinfunction "2_2") (pintype "passive"))
      (node (ref "C6") (pin "2") (pinfunction "2_2") (pintype "passive"))
      (node (ref "C7") (pin "2") (pinfunction "2_2") (pintype "passive"))
      (node (ref "C8") (pin "2") (pinfunction "2_2") (pintype "passive"))
      (node (ref "C9") (pin "2") (pinfunction "2_2") (pintype "passive"))
      (node (ref "D14") (pin "A") (pinfunction "A_A") (pintype "passive"))
      (node (ref "D3") (pin "A") (pinfunction "A_A") (pintype "passive"))
      (node (ref "D4") (pin "A") (pinfunction "A_A") (pintype "passive"))
      (node (ref "IC1") (pin "3") (pinfunction "GND_3") (pintype "input"))
      (node (ref "IC10") (pin "3") (pinfunction "GND_3") (pintype "power_in"))
      (node (ref "IC10") (pin "5") (pinfunction "EN_5") (pintype "input"))
      (node (ref "IC10") (pin "6") (pinfunction "GND_6") (pintype "power_in"))
      (node (ref "IC11") (pin "1") (pinfunction "GND_1") (pintype "input"))
      (node (ref "IC12") (pin "2") (pinfunction "V-_2") (pintype "bidirectional"))
      (node (ref "IC13") (pin "2") (pinfunction "V-_2") (pintype "bidirectional"))
      (node (ref "IC14") (pin "5") (pinfunction "SOURCE2_5") (pintype "bidirectional"))
      (node (ref "IC14") (pin "7") (pinfunction "SOURCE1_7") (pintype "bidirectional"))
      (node (ref "IC15") (pin "2") (pinfunction "V-_2") (pintype "bidirectional"))
      (node (ref "IC2") (pin "3") (pinfunction "GND_3") (pintype "input"))
      (node (ref "IC3") (pin "3") (pinfunction "GND_3") (pintype "input"))
      (node (ref "IC4") (pin "3") (pinfunction "GND_3") (pintype "input"))
      (node (ref "IC5") (pin "11") (pinfunction "V-_11") (pintype "power_in"))
      (node (ref "IC6") (pin "11") (pinfunction "V-_11") (pintype "power_in"))
      (node (ref "IC7") (pin "1") (pinfunction "GND_1") (pintype "input"))
      (node (ref "IC8") (pin "1") (pinfunction "GND_1") (pintype "input"))
      (node (ref "IC9") (pin "11") (pinfunction "V-_11") (pintype "power_in"))
      (node (ref "J1") (pin "18") (pinfunction "18_18") (pintype "passive"))
      (node (ref "J1") (pin "26") (pinfunction "26_26") (pintype "passive"))
      (node (ref "J1") (pin "3") (pinfunction "3_3") (pintype "passive"))
      (node (ref "J1") (pin "40") (pinfunction "40_40") (pintype "passive"))
      (node (ref "J1") (pin "48") (pinfunction "48_48") (pintype "passive"))
      (node (ref "J1") (pin "49") (pinfunction "49_49") (pintype "passive"))
      (node (ref "JP2") (pin "2") (pinfunction "2_2") (pintype "passive"))
      (node (ref "JP8") (pin "2") (pinfunction "2_2") (pintype "passive"))
      (node (ref "LED1") (pin "C") (pinfunction "C_C") (pintype "passive"))
      (node (ref "LED2") (pin "C") (pinfunction "C_C") (pintype "passive"))
      (node (ref "PS1") (pin "3") (pinfunction "GND_3") (pintype "power_in"))
      (node (ref "Q4") (pin "2") (pinfunction "S_2") (pintype "passive"))
      (node (ref "R10") (pin "1") (pinfunction "1_1") (pintype "passive"))
      (node (ref "R12") (pin "1") (pinfunction "1_1") (pintype "passive"))
      (node (ref "R14") (pin "1") (pinfunction "1_1") (pintype "passive"))
      (node (ref "R16") (pin "1") (pinfunction "1_1") (pintype "passive"))
      (node (ref "R18") (pin "2") (pinfunction "2_2") (pintype "passive"))
      (node (ref "R19") (pin "1") (pinfunction "1_1") (pintype "passive"))
      (node (ref "R2") (pin "1") (pinfunction "1_1") (pintype "passive"))
      (node (ref "R24") (pin "2") (pinfunction "2_2") (pintype "passive"))
      (node (ref "R25") (pin "1") (pinfunction "1_1") (pintype "passive"))
      (node (ref "R30") (pin "2") (pinfunction "2_2") (pintype "passive"))
      (node (ref "R31") (pin "1") (pinfunction "1_1") (pintype "passive"))
      (node (ref "R36") (pin "2") (pinfunction "2_2") (pintype "passive"))
      (node (ref "R37") (pin "1") (pinfunction "1_1") (pintype "passive"))
      (node (ref "R4") (pin "1") (pinfunction "1_1") (pintype "passive"))
      (node (ref "R50") (pin "1") (pinfunction "1_1") (pintype "passive"))
      (node (ref "R55") (pin "1") (pinfunction "1_1") (pintype "passive"))
      (node (ref "R56") (pin "1") (pinfunction "1_1") (pintype "passive"))
      (node (ref "R57") (pin "1") (pinfunction "1_1") (pintype "passive"))
      (node (ref "R58") (pin "1") (pinfunction "1_1") (pintype "passive"))
      (node (ref "R6") (pin "1") (pinfunction "1_1") (pintype "passive"))
      (node (ref "R63") (pin "1") (pinfunction "1_1") (pintype "passive"))
      (node (ref "R64") (pin "1") (pinfunction "1_1") (pintype "passive"))
      (node (ref "R65") (pin "1") (pinfunction "1_1") (pintype "passive"))
      (node (ref "R66") (pin "1") (pinfunction "1_1") (pintype "passive"))
      (node (ref "R67") (pin "2") (pinfunction "2_2") (pintype "passive"))
      (node (ref "R73") (pin "2") (pinfunction "2_2") (pintype "passive"))
      (node (ref "R78") (pin "2") (pinfunction "2_2") (pintype "passive"))
      (node (ref "R8") (pin "1") (pinfunction "1_1") (pintype "passive"))
      (node (ref "R80") (pin "1") (pinfunction "1_1") (pintype "passive"))
      (node (ref "R84") (pin "1") (pinfunction "1_1") (pintype "passive"))
      (node (ref "R85") (pin "1") (pinfunction "1_1") (pintype "passive"))
      (node (ref "R86") (pin "1") (pinfunction "1_1") (pintype "passive"))
      (node (ref "R95") (pin "2") (pinfunction "2_2") (pintype "passive"))
      (node (ref "R96") (pin "1") (pinfunction "1_1") (pintype "passive"))
      (node (ref "S1") (pin "2") (pinfunction "S_2") (pintype "passive"))
      (node (ref "S2") (pin "2") (pinfunction "S_2") (pintype "passive"))
      (node (ref "S3") (pin "2") (pinfunction "S_2") (pintype "passive"))
      (node (ref "S4") (pin "2") (pinfunction "S_2") (pintype "passive"))
      (node (ref "S5") (pin "2") (pinfunction "S_2") (pintype "passive"))
      (node (ref "S6") (pin "2") (pinfunction "S_2") (pintype "passive"))
      (node (ref "S7") (pin "2") (pinfunction "S_2") (pintype "passive"))
      (node (ref "S8") (pin "2") (pinfunction "S_2") (pintype "passive"))
      (node (ref "U$1") (pin "GND") (pinfunction "GND_GND") (pintype "bidirectional"))
      (node (ref "U$1") (pin "GND2") (pinfunction "GND2_GND2") (pintype "bidirectional"))
      (node (ref "U$1") (pin "GND3") (pinfunction "GND3_GND3") (pintype "bidirectional"))
      (node (ref "U$3") (pin "GND") (pinfunction "GND_GND") (pintype "bidirectional"))
      (node (ref "U$3") (pin "GND2") (pinfunction "GND2_GND2") (pintype "bidirectional"))
      (node (ref "U1") (pin "2") (pinfunction "GND_2") (pintype "power_in"))
      (node (ref "ULN2803") (pin "9") (pinfunction "VS_9") (pintype "passive"))
    )
    (net (code "36") (name "HC1-IN") (class "Default")
      (node (ref "R93") (pin "1") (pinfunction "1_1") (pintype "passive"))
      (node (ref "U$1") (pin "1/TX") (pinfunction "1/TX_1/TX") (pintype "bidirectional"))
    )
    (net (code "37") (name "HC1-OUT") (class "Default")
      (node (ref "IC14") (pin "8") (pinfunction "DRAIN1_8") (pintype "bidirectional"))
      (node (ref "J1") (pin "25") (pinfunction "25_25") (pintype "passive"))
    )
    (net (code "38") (name "HC2-IN") (class "Default")
      (node (ref "JMP1") (pin "1") (pinfunction "1_1") (pintype "passive"))
      (node (ref "R94") (pin "1") (pinfunction "1_1") (pintype "passive"))
    )
    (net (code "39") (name "HC2-OUT") (class "Default")
      (node (ref "IC14") (pin "6") (pinfunction "DRAIN2_6") (pintype "bidirectional"))
      (node (ref "J1") (pin "24") (pinfunction "24_24") (pintype "passive"))
    )
    (net (code "40") (name "IAT-ECU") (class "Default")
      (node (ref "IC5") (pin "13") (pinfunction "-IN_13") (pintype "input"))
      (node (ref "IC5") (pin "14") (pinfunction "OUT_14") (pintype "output"))
      (node (ref "U$1") (pin "14/A0") (pinfunction "14/A0_14/A0") (pintype "bidirectional"))
    )
    (net (code "41") (name "IAT-IN") (class "Default")
      (node (ref "C5") (pin "1") (pinfunction "1_1") (pintype "passive"))
      (node (ref "J1") (pin "37") (pinfunction "37_37") (pintype "passive"))
      (node (ref "R43") (pin "1") (pinfunction "1_1") (pintype "passive"))
      (node (ref "R48") (pin "1") (pinfunction "1_1") (pintype "passive"))
    )
    (net (code "42") (name "IAT-OUT") (class "Default")
      (node (ref "C6") (pin "1") (pinfunction "1_1") (pintype "passive"))
      (node (ref "IC12") (pin "6") (pinfunction "I/O_6") (pintype "bidirectional"))
      (node (ref "R43") (pin "2") (pinfunction "2_2") (pintype "passive"))
      (node (ref "R54") (pin "2") (pinfunction "2_2") (pintype "passive"))
    )
    (net (code "43") (name "IGN-1") (class "Default")
      (node (ref "R38") (pin "1") (pinfunction "1_1") (pintype "passive"))
      (node (ref "U$1") (pin "31/A12") (pinfunction "31/A12_31/A12") (pintype "bidirectional"))
    )
    (net (code "44") (name "IGN-1-OUT") (class "Default")
      (node (ref "J1") (pin "31") (pinfunction "31_31") (pintype "passive"))
      (node (ref "R39") (pin "2") (pinfunction "2_2") (pintype "passive"))
    )
    (net (code "45") (name "IGN-2") (class "Default")
      (node (ref "R35") (pin "1") (pinfunction "1_1") (pintype "passive"))
      (node (ref "U$1") (pin "38/A19") (pinfunction "38/A19_38/A19") (pintype "bidirectional"))
    )
    (net (code "46") (name "IGN-2-OUT") (class "Default")
      (node (ref "J1") (pin "32") (pinfunction "32_32") (pintype "passive"))
      (node (ref "R40") (pin "2") (pinfunction "2_2") (pintype "passive"))
    )
    (net (code "47") (name "IGN-3") (class "Default")
      (node (ref "R32") (pin "1") (pinfunction "1_1") (pintype "passive"))
      (node (ref "U$1") (pin "30") (pinfunction "30_30") (pintype "bidirectional"))
    )
    (net (code "48") (name "IGN-3-OUT") (class "Default")
      (node (ref "J1") (pin "33") (pinfunction "33_33") (pintype "passive"))
      (node (ref "R33") (pin "2") (pinfunction "2_2") (pintype "passive"))
    )
    (net (code "49") (name "IGN-4") (class "Default")
      (node (ref "R29") (pin "1") (pinfunction "1_1") (pintype "passive"))
      (node (ref "U$1") (pin "29") (pinfunction "29_29") (pintype "bidirectional"))
    )
    (net (code "50") (name "IGN-4-OUT") (class "Default")
      (node (ref "J1") (pin "34") (pinfunction "34_34") (pintype "passive"))
      (node (ref "R34") (pin "2") (pinfunction "2_2") (pintype "passive"))
    )
    (net (code "51") (name "IGN-5") (class "Default")
      (node (ref "R26") (pin "1") (pinfunction "1_1") (pintype "passive"))
      (node (ref "U$1") (pin "32/A13") (pinfunction "32/A13_32/A13") (pintype "bidirectional"))
    )
    (net (code "52") (name "IGN-5-OUT") (class "Default")
      (node (ref "J1") (pin "54") (pinfunction "54_54") (pintype "passive"))
      (node (ref "R27") (pin "2") (pinfunction "2_2") (pintype "passive"))
    )
    (net (code "53") (name "IGN-6") (class "Default")
      (node (ref "R23") (pin "1") (pinfunction "1_1") (pintype "passive"))
      (node (ref "U$1") (pin "33/A14") (pinfunction "33/A14_33/A14") (pintype "bidirectional"))
    )
    (net (code "54") (name "IGN-6-OUT") (class "Default")
      (node (ref "J1") (pin "55") (pinfunction "55_55") (pintype "passive"))
      (node (ref "R28") (pin "2") (pinfunction "2_2") (pintype "passive"))
    )
    (net (code "55") (name "IGN-7") (class "Default")
      (node (ref "R20") (pin "1") (pinfunction "1_1") (pintype "passive"))
      (node (ref "U$1") (pin "25") (pinfunction "25_25") (pintype "bidirectional"))
    )
    (net (code "56") (name "IGN-7-OUT") (class "Default")
      (node (ref "J1") (pin "56") (pinfunction "56_56") (pintype "passive"))
      (node (ref "R21") (pin "2") (pinfunction "2_2") (pintype "passive"))
    )
    (net (code "57") (name "IGN-8") (class "Default")
      (node (ref "R17") (pin "1") (pinfunction "1_1") (pintype "passive"))
      (node (ref "U$1") (pin "26") (pinfunction "26_26") (pintype "bidirectional"))
    )
    (net (code "58") (name "IGN-8-OUT") (class "Default")
      (node (ref "J1") (pin "57") (pinfunction "57_57") (pintype "passive"))
      (node (ref "R22") (pin "2") (pinfunction "2_2") (pintype "passive"))
    )
    (net (code "59") (name "INJ-1") (class "Default")
      (node (ref "R1") (pin "1") (pinfunction "1_1") (pintype "passive"))
      (node (ref "U$1") (pin "5") (pinfunction "5_5") (pintype "bidirectional"))
    )
    (net (code "60") (name "INJ-1-OUT") (class "Default")
      (node (ref "J1") (pin "27") (pinfunction "27_27") (pintype "passive"))
      (node (ref "S1") (pin "3") (pinfunction "D_3") (pintype "passive"))
    )
    (net (code "61") (name "INJ-2") (class "Default")
      (node (ref "R3") (pin "1") (pinfunction "1_1") (pintype "passive"))
      (node (ref "U$1") (pin "6") (pinfunction "6_6") (pintype "bidirectional"))
    )
    (net (code "62") (name "INJ-2-OUT") (class "Default")
      (node (ref "J1") (pin "28") (pinfunction "28_28") (pintype "passive"))
      (node (ref "S2") (pin "3") (pinfunction "D_3") (pintype "passive"))
    )
    (net (code "63") (name "INJ-3") (class "Default")
      (node (ref "R5") (pin "1") (pinfunction "1_1") (pintype "passive"))
      (node (ref "U$1") (pin "7") (pinfunction "7_7") (pintype "bidirectional"))
    )
    (net (code "64") (name "INJ-3-OUT") (class "Default")
      (node (ref "J1") (pin "29") (pinfunction "29_29") (pintype "passive"))
      (node (ref "S3") (pin "3") (pinfunction "D_3") (pintype "passive"))
    )
    (net (code "65") (name "INJ-4") (class "Default")
      (node (ref "R7") (pin "1") (pinfunction "1_1") (pintype "passive"))
      (node (ref "U$1") (pin "8") (pinfunction "8_8") (pintype "bidirectional"))
    )
    (net (code "66") (name "INJ-4-OUT") (class "Default")
      (node (ref "J1") (pin "30") (pinfunction "30_30") (pintype "passive"))
      (node (ref "S4") (pin "3") (pinfunction "D_3") (pintype "passive"))
    )
    (net (code "67") (name "INJ-5") (class "Default")
      (node (ref "R9") (pin "1") (pinfunction "1_1") (pintype "passive"))
      (node (ref "U$1") (pin "22/A8") (pinfunction "22/A8_22/A8") (pintype "bidirectional"))
    )
    (net (code "68") (name "INJ-5-OUT") (class "Default")
      (node (ref "J1") (pin "58") (pinfunction "58_58") (pintype "passive"))
      (node (ref "S5") (pin "3") (pinfunction "D_3") (pintype "passive"))
    )
    (net (code "69") (name "INJ-6") (class "Default")
      (node (ref "R11") (pin "1") (pinfunction "1_1") (pintype "passive"))
      (node (ref "U$1") (pin "21/A7") (pinfunction "21/A7_21/A7") (pintype "bidirectional"))
    )
    (net (code "70") (name "INJ-6-OUT") (class "Default")
      (node (ref "J1") (pin "59") (pinfunction "59_59") (pintype "passive"))
      (node (ref "S6") (pin "3") (pinfunction "D_3") (pintype "passive"))
    )
    (net (code "71") (name "INJ-7") (class "Default")
      (node (ref "R13") (pin "1") (pinfunction "1_1") (pintype "passive"))
      (node (ref "U$1") (pin "11/MOSI") (pinfunction "11/MOSI_11/MOSI") (pintype "bidirectional"))
    )
    (net (code "72") (name "INJ-7-OUT") (class "Default")
      (node (ref "J1") (pin "60") (pinfunction "60_60") (pintype "passive"))
      (node (ref "S7") (pin "3") (pinfunction "D_3") (pintype "passive"))
    )
    (net (code "73") (name "INJ-8") (class "Default")
      (node (ref "R15") (pin "1") (pinfunction "1_1") (pintype "passive"))
      (node (ref "U$1") (pin "12/MISO") (pinfunction "12/MISO_12/MISO") (pintype "bidirectional"))
    )
    (net (code "74") (name "INJ-8-OUT") (class "Default")
      (node (ref "J1") (pin "53") (pinfunction "53_53") (pintype "passive"))
      (node (ref "S8") (pin "3") (pinfunction "D_3") (pintype "passive"))
    )
    (net (code "75") (name "MAP-ECU") (class "Default")
      (node (ref "IC6") (pin "8") (pinfunction "OUT_8") (pintype "output"))
      (node (ref "IC6") (pin "9") (pinfunction "-IN_9") (pintype "input"))
      (node (ref "U$1") (pin "17/A3") (pinfunction "17/A3_17/A3") (pintype "bidirectional"))
    )
    (net (code "76") (name "MAP-IN") (class "Default")
      (node (ref "C11") (pin "1") (pinfunction "1_1") (pintype "passive"))
      (node (ref "J1") (pin "38") (pinfunction "38_38") (pintype "passive"))
      (node (ref "R46") (pin "1") (pinfunction "1_1") (pintype "passive"))
    )
    (net (code "77") (name "MAP-OUT") (class "Default")
      (node (ref "C12") (pin "1") (pinfunction "1_1") (pintype "passive"))
      (node (ref "IC12") (pin "4") (pinfunction "I/O_4_4") (pintype "bidirectional"))
      (node (ref "R46") (pin "2") (pinfunction "2_2") (pintype "passive"))
      (node (ref "R61") (pin "2") (pinfunction "2_2") (pintype "passive"))
    )
    (net (code "78") (name "Net-(C1-Pad1)") (class "Default")
      (node (ref "C1") (pin "1") (pinfunction "1_1") (pintype "passive"))
      (node (ref "R41") (pin "1") (pinfunction "1_1") (pintype "passive"))
      (node (ref "R49") (pin "1") (pinfunction "1_1") (pintype "passive"))
      (node (ref "R50") (pin "2") (pinfunction "2_2") (pintype "passive"))
    )
    (net (code "79") (name "Net-(IC1-IN_A)") (class "Default")
      (node (ref "IC1") (pin "2") (pinfunction "IN_A_2") (pintype "input"))
      (node (ref "R17") (pin "2") (pinfunction "2_2") (pintype "passive"))
      (node (ref "R18") (pin "1") (pinfunction "1_1") (pintype "passive"))
    )
    (net (code "80") (name "Net-(IC1-IN_B)") (class "Default")
      (node (ref "IC1") (pin "4") (pinfunction "IN_B_4") (pintype "input"))
      (node (ref "R19") (pin "2") (pinfunction "2_2") (pintype "passive"))
      (node (ref "R20") (pin "2") (pinfunction "2_2") (pintype "passive"))
    )
    (net (code "81") (name "Net-(IC1-OUT_A)") (class "Default")
      (node (ref "IC1") (pin "7") (pinfunction "OUT_A_7") (pintype "input"))
      (node (ref "R22") (pin "1") (pinfunction "1_1") (pintype "passive"))
    )
    (net (code "82") (name "Net-(IC1-OUT_B)") (class "Default")
      (node (ref "IC1") (pin "5") (pinfunction "OUT_B_5") (pintype "input"))
      (node (ref "R21") (pin "1") (pinfunction "1_1") (pintype "passive"))
    )
    (net (code "83") (name "Net-(IC2-IN_A)") (class "Default")
      (node (ref "IC2") (pin "2") (pinfunction "IN_A_2") (pintype "input"))
      (node (ref "R23") (pin "2") (pinfunction "2_2") (pintype "passive"))
      (node (ref "R24") (pin "1") (pinfunction "1_1") (pintype "passive"))
    )
    (net (code "84") (name "Net-(IC2-IN_B)") (class "Default")
      (node (ref "IC2") (pin "4") (pinfunction "IN_B_4") (pintype "input"))
      (node (ref "R25") (pin "2") (pinfunction "2_2") (pintype "passive"))
      (node (ref "R26") (pin "2") (pinfunction "2_2") (pintype "passive"))
    )
    (net (code "85") (name "Net-(IC2-OUT_A)") (class "Default")
      (node (ref "IC2") (pin "7") (pinfunction "OUT_A_7") (pintype "input"))
      (node (ref "R28") (pin "1") (pinfunction "1_1") (pintype "passive"))
    )
    (net (code "86") (name "Net-(IC2-OUT_B)") (class "Default")
      (node (ref "IC2") (pin "5") (pinfunction "OUT_B_5") (pintype "input"))
      (node (ref "R27") (pin "1") (pinfunction "1_1") (pintype "passive"))
    )
    (net (code "87") (name "Net-(IC3-IN_A)") (class "Default")
      (node (ref "IC3") (pin "2") (pinfunction "IN_A_2") (pintype "input"))
      (node (ref "R29") (pin "2") (pinfunction "2_2") (pintype "passive"))
      (node (ref "R30") (pin "1") (pinfunction "1_1") (pintype "passive"))
    )
    (net (code "88") (name "Net-(IC3-IN_B)") (class "Default")
      (node (ref "IC3") (pin "4") (pinfunction "IN_B_4") (pintype "input"))
      (node (ref "R31") (pin "2") (pinfunction "2_2") (pintype "passive"))
      (node (ref "R32") (pin "2") (pinfunction "2_2") (pintype "passive"))
    )
    (net (code "89") (name "Net-(IC3-OUT_A)") (class "Default")
      (node (ref "IC3") (pin "7") (pinfunction "OUT_A_7") (pintype "input"))
      (node (ref "R34") (pin "1") (pinfunction "1_1") (pintype "passive"))
    )
    (net (code "90") (name "Net-(IC3-OUT_B)") (class "Default")
      (node (ref "IC3") (pin "5") (pinfunction "OUT_B_5") (pintype "input"))
      (node (ref "R33") (pin "1") (pinfunction "1_1") (pintype "passive"))
    )
    (net (code "91") (name "Net-(IC4-IN_A)") (class "Default")
      (node (ref "IC4") (pin "2") (pinfunction "IN_A_2") (pintype "input"))
      (node (ref "R35") (pin "2") (pinfunction "2_2") (pintype "passive"))
      (node (ref "R36") (pin "1") (pinfunction "1_1") (pintype "passive"))
    )
    (net (code "92") (name "Net-(IC4-IN_B)") (class "Default")
      (node (ref "IC4") (pin "4") (pinfunction "IN_B_4") (pintype "input"))
      (node (ref "R37") (pin "2") (pinfunction "2_2") (pintype "passive"))
      (node (ref "R38") (pin "2") (pinfunction "2_2") (pintype "passive"))
    )
    (net (code "93") (name "Net-(IC4-OUT_A)") (class "Default")
      (node (ref "IC4") (pin "7") (pinfunction "OUT_A_7") (pintype "input"))
      (node (ref "R40") (pin "1") (pinfunction "1_1") (pintype "passive"))
    )
    (net (code "94") (name "Net-(IC4-OUT_B)") (class "Default")
      (node (ref "IC4") (pin "5") (pinfunction "OUT_B_5") (pintype "input"))
      (node (ref "R39") (pin "1") (pinfunction "1_1") (pintype "passive"))
    )
    (net (code "95") (name "Net-(IC5A-+IN)") (class "Default")
      (node (ref "IC5") (pin "3") (pinfunction "+IN_3") (pintype "input"))
      (node (ref "R51") (pin "1") (pinfunction "1_1") (pintype "passive"))
      (node (ref "R58") (pin "2") (pinfunction "2_2") (pintype "passive"))
    )
    (net (code "96") (name "Net-(IC5B-+IN)") (class "Default")
      (node (ref "IC5") (pin "5") (pinfunction "+IN_5") (pintype "input"))
      (node (ref "R52") (pin "1") (pinfunction "1_1") (pintype "passive"))
      (node (ref "R57") (pin "2") (pinfunction "2_2") (pintype "passive"))
    )
    (net (code "97") (name "Net-(IC5C-+IN)") (class "Default")
      (node (ref "IC5") (pin "10") (pinfunction "+IN_10") (pintype "input"))
      (node (ref "R53") (pin "1") (pinfunction "1_1") (pintype "passive"))
      (node (ref "R56") (pin "2") (pinfunction "2_2") (pintype "passive"))
    )
    (net (code "98") (name "Net-(IC5D-+IN)") (class "Default")
      (node (ref "IC5") (pin "12") (pinfunction "+IN_12") (pintype "input"))
      (node (ref "R54") (pin "1") (pinfunction "1_1") (pintype "passive"))
      (node (ref "R55") (pin "2") (pinfunction "2_2") (pintype "passive"))
    )
    (net (code "99") (name "Net-(IC6A-+IN)") (class "Default")
      (node (ref "IC6") (pin "3") (pinfunction "+IN_3") (pintype "input"))
      (node (ref "R59") (pin "1") (pinfunction "1_1") (pintype "passive"))
      (node (ref "R66") (pin "2") (pinfunction "2_2") (pintype "passive"))
    )
    (net (code "100") (name "Net-(IC6B-+IN)") (class "Default")
      (node (ref "IC6") (pin "5") (pinfunction "+IN_5") (pintype "input"))
      (node (ref "R60") (pin "1") (pinfunction "1_1") (pintype "passive"))
      (node (ref "R65") (pin "2") (pinfunction "2_2") (pintype "passive"))
    )
    (net (code "101") (name "Net-(IC6C-+IN)") (class "Default")
      (node (ref "IC6") (pin "10") (pinfunction "+IN_10") (pintype "input"))
      (node (ref "R61") (pin "1") (pinfunction "1_1") (pintype "passive"))
      (node (ref "R64") (pin "2") (pinfunction "2_2") (pintype "passive"))
    )
    (net (code "102") (name "Net-(IC6D-+IN)") (class "Default")
      (node (ref "IC6") (pin "12") (pinfunction "+IN_12") (pintype "input"))
      (node (ref "R62") (pin "1") (pinfunction "1_1") (pintype "passive"))
      (node (ref "R63") (pin "2") (pinfunction "2_2") (pintype "passive"))
    )
    (net (code "103") (name "Net-(IC9A-+IN)") (class "Default")
      (node (ref "IC9") (pin "3") (pinfunction "+IN_3") (pintype "input"))
      (node (ref "R79") (pin "1") (pinfunction "1_1") (pintype "passive"))
      (node (ref "R80") (pin "2") (pinfunction "2_2") (pintype "passive"))
    )
    (net (code "104") (name "Net-(IC9B-+IN)") (class "Default")
      (node (ref "IC9") (pin "5") (pinfunction "+IN_5") (pintype "input"))
      (node (ref "R81") (pin "1") (pinfunction "1_1") (pintype "passive"))
      (node (ref "R84") (pin "2") (pinfunction "2_2") (pintype "passive"))
    )
    (net (code "105") (name "Net-(IC9C-+IN)") (class "Default")
      (node (ref "IC9") (pin "10") (pinfunction "+IN_10") (pintype "input"))
      (node (ref "R82") (pin "1") (pinfunction "1_1") (pintype "passive"))
      (node (ref "R85") (pin "2") (pinfunction "2_2") (pintype "passive"))
    )
    (net (code "106") (name "Net-(IC9D-+IN)") (class "Default")
      (node (ref "IC9") (pin "12") (pinfunction "+IN_12") (pintype "input"))
      (node (ref "R83") (pin "1") (pinfunction "1_1") (pintype "passive"))
      (node (ref "R86") (pin "2") (pinfunction "2_2") (pintype "passive"))
    )
    (net (code "107") (name "Net-(IC10-FB)") (class "Default")
      (node (ref "IC10") (pin "4") (pinfunction "FB_4") (pintype "input"))
      (node (ref "R67") (pin "1") (pinfunction "1_1") (pintype "passive"))
      (node (ref "R68") (pin "1") (pinfunction "1_1") (pintype "passive"))
    )
    (net (code "108") (name "Net-(IC10-OUT)") (class "Default")
      (node (ref "D4") (pin "C") (pinfunction "C_C") (pintype "passive"))
      (node (ref "IC10") (pin "2") (pinfunction "OUT_2") (pintype "output"))
      (node (ref "L2") (pin "1") (pinfunction "1_1") (pintype "passive"))
    )
    (net (code "109") (name "Net-(IC14-IN1{slash}VSUPPLY1)") (class "Default")
      (node (ref "IC14") (pin "1") (pinfunction "IN1/VSUPPLY1_1") (pintype "bidirectional"))
      (node (ref "R93") (pin "2") (pinfunction "2_2") (pintype "passive"))
      (node (ref "R95") (pin "1") (pinfunction "1_1") (pintype "passive"))
    )
    (net (code "110") (name "Net-(IC14-IN2{slash}VSUPPLY2)") (class "Default")
      (node (ref "IC14") (pin "3") (pinfunction "IN2/VSUPPLY2_3") (pintype "bidirectional"))
      (node (ref "R94") (pin "2") (pinfunction "2_2") (pintype "passive"))
      (node (ref "R96") (pin "2") (pinfunction "2_2") (pintype "passive"))
    )
    (net (code "111") (name "Net-(JP3-Pad2)") (class "Default")
      (node (ref "JP3") (pin "2") (pinfunction "2_2") (pintype "passive"))
      (node (ref "JP4") (pin "1") (pinfunction "1_1") (pintype "passive"))
    )
    (net (code "112") (name "Net-(JP3-Pad3)") (class "Default")
      (node (ref "JP3") (pin "3") (pinfunction "3_3") (pintype "passive"))
      (node (ref "JP5") (pin "1") (pinfunction "1_1") (pintype "passive"))
    )
    (net (code "113") (name "Net-(JP6-Pad2)") (class "Default")
      (node (ref "JP6") (pin "2") (pinfunction "2_2") (pintype "passive"))
      (node (ref "R70") (pin "2") (pinfunction "2_2") (pintype "passive"))
    )
    (net (code "114") (name "Net-(JP7-Pad2)") (class "Default")
      (node (ref "JP7") (pin "2") (pinfunction "2_2") (pintype "passive"))
      (node (ref "R71") (pin "1") (pinfunction "1_1") (pintype "passive"))
    )
    (net (code "115") (name "Net-(JP9-Pad2)") (class "Default")
      (node (ref "JP9") (pin "2") (pinfunction "2_2") (pintype "passive"))
      (node (ref "R91") (pin "2") (pinfunction "2_2") (pintype "passive"))
    )
    (net (code "116") (name "Net-(JP10-Pad2)") (class "Default")
      (node (ref "JP10") (pin "2") (pinfunction "2_2") (pintype "passive"))
      (node (ref "R92") (pin "2") (pinfunction "2_2") (pintype "passive"))
    )
    (net (code "117") (name "Net-(LED1-PadA)") (class "Default")
      (node (ref "LED1") (pin "A") (pinfunction "A_A") (pintype "passive"))
      (node (ref "R69") (pin "2") (pinfunction "2_2") (pintype "passive"))
    )
    (net (code "118") (name "Net-(LED2-PadA)") (class "Default")
      (node (ref "LED2") (pin "A") (pinfunction "A_A") (pintype "passive"))
      (node (ref "R76") (pin "2") (pinfunction "2_2") (pintype "passive"))
    )
    (net (code "119") (name "Net-(PS1-VOUT)") (class "Default")
      (node (ref "C29") (pin "2") (pinfunction "2_2") (pintype "passive"))
      (node (ref "PS1") (pin "4") (pinfunction "VOUT_4") (pintype "output"))
      (node (ref "R90") (pin "2") (pinfunction "2_2") (pintype "passive"))
    )
    (net (code "120") (name "Net-(Q4-G)") (class "Default")
      (node (ref "Q4") (pin "1") (pinfunction "G_1") (pintype "passive"))
      (node (ref "R77") (pin "1") (pinfunction "1_1") (pintype "passive"))
      (node (ref "R78") (pin "1") (pinfunction "1_1") (pintype "passive"))
    )
    (net (code "121") (name "Net-(S1-IN)") (class "Default")
      (node (ref "R1") (pin "2") (pinfunction "2_2") (pintype "passive"))
      (node (ref "R2") (pin "2") (pinfunction "2_2") (pintype "passive"))
      (node (ref "S1") (pin "1") (pinfunction "IN_1") (pintype "input"))
    )
    (net (code "122") (name "Net-(S2-IN)") (class "Default")
      (node (ref "R3") (pin "2") (pinfunction "2_2") (pintype "passive"))
      (node (ref "R4") (pin "2") (pinfunction "2_2") (pintype "passive"))
      (node (ref "S2") (pin "1") (pinfunction "IN_1") (pintype "input"))
    )
    (net (code "123") (name "Net-(S3-IN)") (class "Default")
      (node (ref "R5") (pin "2") (pinfunction "2_2") (pintype "passive"))
      (node (ref "R6") (pin "2") (pinfunction "2_2") (pintype "passive"))
      (node (ref "S3") (pin "1") (pinfunction "IN_1") (pintype "input"))
    )
    (net (code "124") (name "Net-(S4-IN)") (class "Default")
      (node (ref "R7") (pin "2") (pinfunction "2_2") (pintype "passive"))
      (node (ref "R8") (pin "2") (pinfunction "2_2") (pintype "passive"))
      (node (ref "S4") (pin "1") (pinfunction "IN_1") (pintype "input"))
    )
    (net (code "125") (name "Net-(S5-IN)") (class "Default")
      (node (ref "R10") (pin "2") (pinfunction "2_2") (pintype "passive"))
      (node (ref "R9") (pin "2") (pinfunction "2_2") (pintype "passive"))
      (node (ref "S5") (pin "1") (pinfunction "IN_1") (pintype "input"))
    )
    (net (code "126") (name "Net-(S6-IN)") (class "Default")
      (node (ref "R11") (pin "2") (pinfunction "2_2") (pintype "passive"))
      (node (ref "R12") (pin "2") (pinfunction "2_2") (pintype "passive"))
      (node (ref "S6") (pin "1") (pinfunction "IN_1") (pintype "input"))
    )
    (net (code "127") (name "Net-(S7-IN)") (class "Default")
      (node (ref "R13") (pin "2") (pinfunction "2_2") (pintype "passive"))
      (node (ref "R14") (pin "2") (pinfunction "2_2") (pintype "passive"))
      (node (ref "S7") (pin "1") (pinfunction "IN_1") (pintype "input"))
    )
    (net (code "128") (name "Net-(S8-IN)") (class "Default")
      (node (ref "R15") (pin "2") (pinfunction "2_2") (pintype "passive"))
      (node (ref "R16") (pin "2") (pinfunction "2_2") (pintype "passive"))
      (node (ref "S8") (pin "1") (pinfunction "IN_1") (pintype "input"))
    )
    (net (code "129") (name "Net-(U1-RS)") (class "Default")
      (node (ref "R73") (pin "1") (pinfunction "1_1") (pintype "passive"))
      (node (ref "U1") (pin "8") (pinfunction "RS_8") (pintype "input"))
    )
    (net (code "130") (name "O2-ECU") (class "Default")
      (node (ref "IC5") (pin "8") (pinfunction "OUT_8") (pintype "output"))
      (node (ref "IC5") (pin "9") (pinfunction "-IN_9") (pintype "input"))
      (node (ref "U$1") (pin "A22/DAC1") (pinfunction "A22/DAC1_A22/DAC1") (pintype "bidirectional"))
    )
    (net (code "131") (name "O2-IN") (class "Default")
      (node (ref "C3") (pin "1") (pinfunction "1_1") (pintype "passive"))
      (node (ref "J1") (pin "39") (pinfunction "39_39") (pintype "passive"))
      (node (ref "R42") (pin "1") (pinfunction "1_1") (pintype "passive"))
    )
    (net (code "132") (name "O2-OUT") (class "Default")
      (node (ref "C4") (pin "1") (pinfunction "1_1") (pintype "passive"))
      (node (ref "IC13") (pin "6") (pinfunction "I/O_6") (pintype "bidirectional"))
      (node (ref "R42") (pin "2") (pinfunction "2_2") (pintype "passive"))
      (node (ref "R53") (pin "2") (pinfunction "2_2") (pintype "passive"))
    )
    (net (code "133") (name "OUT-SELECT") (class "Default")
      (node (ref "C25") (pin "1") (pinfunction "1_1") (pintype "passive"))
      (node (ref "C26") (pin "1") (pinfunction "1_1") (pintype "passive"))
      (node (ref "IC1") (pin "6") (pinfunction "VDD_6") (pintype "input"))
      (node (ref "IC2") (pin "6") (pinfunction "VDD_6") (pintype "input"))
      (node (ref "IC3") (pin "6") (pinfunction "VDD_6") (pintype "input"))
      (node (ref "IC4") (pin "6") (pinfunction "VDD_6") (pintype "input"))
      (node (ref "JP1") (pin "2") (pinfunction "2_2") (pintype "passive"))
    )
    (net (code "134") (name "RST_CPU") (class "Default")
      (node (ref "C21") (pin "1") (pinfunction "1_1") (pintype "passive"))
      (node (ref "D1") (pin "A") (pinfunction "A_A") (pintype "passive"))
      (node (ref "R75") (pin "2") (pinfunction "2_2") (pintype "passive"))
      (node (ref "U$1") (pin "RESET") (pinfunction "RESET_RESET") (pintype "bidirectional"))
    )
    (net (code "135") (name "RX") (class "Default")
      (node (ref "JP8") (pin "3") (pinfunction "3_3") (pintype "passive"))
      (node (ref "U$1") (pin "9/CS") (pinfunction "9/CS_9/CS") (pintype "bidirectional"))
    )
    (net (code "136") (name "RX1") (class "Default")
      (node (ref "U$1") (pin "0/RX") (pinfunction "0/RX_0/RX") (pintype "bidirectional"))
    )
    (net (code "137") (name "SPARE-CPU") (class "Default")
      (node (ref "U$1") (pin "2") (pinfunction "2_2") (pintype "bidirectional"))
      (node (ref "ULN2803") (pin "7") (pinfunction "I7_7") (pintype "input"))
      (node (ref "ULN2803") (pin "8") (pinfunction "I8_8") (pintype "input"))
    )
    (net (code "138") (name "SPARE-OUT") (class "Default")
      (node (ref "J1") (pin "6") (pinfunction "6_6") (pintype "passive"))
      (node (ref "ULN2803") (pin "11") (pinfunction "O8_11") (pintype "open_collector"))
      (node (ref "ULN2803") (pin "12") (pinfunction "O7_12") (pintype "open_collector"))
    )
    (net (code "139") (name "SPARE2-CPU") (class "Default")
      (node (ref "U$1") (pin "39/A20") (pinfunction "39/A20_39/A20") (pintype "bidirectional"))
      (node (ref "ULN2803") (pin "3") (pinfunction "I3_3") (pintype "input"))
      (node (ref "ULN2803") (pin "4") (pinfunction "I4_4") (pintype "input"))
    )
    (net (code "140") (name "SPARE2-OUT") (class "Default")
      (node (ref "J1") (pin "8") (pinfunction "8_8") (pintype "passive"))
      (node (ref "ULN2803") (pin "15") (pinfunction "O4_15") (pintype "open_collector"))
      (node (ref "ULN2803") (pin "16") (pinfunction "O3_16") (pintype "open_collector"))
    )
    (net (code "141") (name "STEP") (class "Default")
      (node (ref "U$1") (pin "35/A16") (pinfunction "35/A16_35/A16") (pintype "bidirectional"))
      (node (ref "U$3") (pin "STEP_N") (pinfunction "STEP_STEP_N") (pintype "bidirectional"))
    )
    (net (code "142") (name "STEP_EN") (class "Default")
      (node (ref "U$1") (pin "24") (pinfunction "24_24") (pintype "bidirectional"))
      (node (ref "U$3") (pin "EN_N") (pinfunction "EN_N_EN_N") (pintype "bidirectional"))
    )
    (net (code "143") (name "TACHO-CPU") (class "Default")
      (node (ref "R77") (pin "2") (pinfunction "2_2") (pintype "passive"))
      (node (ref "U$1") (pin "28") (pinfunction "28_28") (pintype "bidirectional"))
    )
    (net (code "144") (name "TACHO-OUT") (class "Default")
      (node (ref "J1") (pin "5") (pinfunction "5_5") (pintype "passive"))
      (node (ref "Q4") (pin "3") (pinfunction "D_3") (pintype "passive"))
      (node (ref "R72") (pin "2") (pinfunction "2_2") (pintype "passive"))
    )
    (net (code "145") (name "TPS-ECU") (class "Default")
      (node (ref "IC5") (pin "6") (pinfunction "-IN_6") (pintype "input"))
      (node (ref "IC5") (pin "7") (pinfunction "OUT_7") (pintype "output"))
      (node (ref "U$1") (pin "16/A2") (pinfunction "16/A2_16/A2") (pintype "bidirectional"))
    )
    (net (code "146") (name "TPS-IN") (class "Default")
      (node (ref "C9") (pin "1") (pinfunction "1_1") (pintype "passive"))
      (node (ref "J1") (pin "36") (pinfunction "36_36") (pintype "passive"))
      (node (ref "R45") (pin "1") (pinfunction "1_1") (pintype "passive"))
    )
    (net (code "147") (name "TPS-OUT") (class "Default")
      (node (ref "C10") (pin "1") (pinfunction "1_1") (pintype "passive"))
      (node (ref "IC12") (pin "3") (pinfunction "I/O_3_3") (pintype "bidirectional"))
      (node (ref "R45") (pin "2") (pinfunction "2_2") (pintype "passive"))
      (node (ref "R52") (pin "2") (pinfunction "2_2") (pintype "passive"))
    )
    (net (code "148") (name "TX") (class "Default")
      (node (ref "JP8") (pin "4") (pinfunction "4_4") (pintype "passive"))
      (node (ref "U$1") (pin "10/CS") (pinfunction "10/CS_10/CS") (pintype "bidirectional"))
    )
    (net (code "149") (name "VR1+") (class "Default")
      (node (ref "J1") (pin "1") (pinfunction "1_1") (pintype "passive"))
      (node (ref "JP5") (pin "2") (pinfunction "2_2") (pintype "passive"))
      (node (ref "JP6") (pin "1") (pinfunction "1_1") (pintype "passive"))
    )
    (net (code "150") (name "VR1+-CPU") (class "Default")
      (node (ref "IC6") (pin "6") (pinfunction "-IN_6") (pintype "input"))
      (node (ref "IC6") (pin "7") (pinfunction "OUT_7") (pintype "output"))
      (node (ref "U$1") (pin "23/A9") (pinfunction "23/A9_23/A9") (pintype "bidirectional"))
    )
    (net (code "151") (name "VR1+OUT") (class "Default")
      (node (ref "C28") (pin "1") (pinfunction "1_1") (pintype "passive"))
      (node (ref "IC13") (pin "1") (pinfunction "I/O_2_1") (pintype "bidirectional"))
      (node (ref "JP2") (pin "4") (pinfunction "4_4") (pintype "passive"))
      (node (ref "JP5") (pin "3") (pinfunction "3_3") (pintype "passive"))
      (node (ref "R60") (pin "2") (pinfunction "2_2") (pintype "passive"))
    )
    (net (code "152") (name "VR1-") (class "Default")
      (node (ref "J1") (pin "10") (pinfunction "10_10") (pintype "passive"))
      (node (ref "JP3") (pin "4") (pinfunction "4_4") (pintype "passive"))
    )
    (net (code "153") (name "VR2+") (class "Default")
      (node (ref "J1") (pin "2") (pinfunction "2_2") (pintype "passive"))
      (node (ref "JP4") (pin "2") (pinfunction "2_2") (pintype "passive"))
      (node (ref "JP7") (pin "1") (pinfunction "1_1") (pintype "passive"))
    )
    (net (code "154") (name "VR2+-CPU") (class "Default")
      (node (ref "IC6") (pin "1") (pinfunction "OUT_1") (pintype "output"))
      (node (ref "IC6") (pin "2") (pinfunction "-IN_2") (pintype "input"))
      (node (ref "U$1") (pin "36/A17") (pinfunction "36/A17_36/A17") (pintype "bidirectional"))
    )
    (net (code "155") (name "VR2+OUT") (class "Default")
      (node (ref "C27") (pin "2") (pinfunction "2_2") (pintype "passive"))
      (node (ref "IC13") (pin "3") (pinfunction "I/O_3_3") (pintype "bidirectional"))
      (node (ref "JP2") (pin "3") (pinfunction "3_3") (pintype "passive"))
      (node (ref "JP4") (pin "3") (pinfunction "3_3") (pintype "passive"))
      (node (ref "R59") (pin "2") (pinfunction "2_2") (pintype "passive"))
    )
    (net (code "156") (name "VR2-") (class "Default")
      (node (ref "J1") (pin "11") (pinfunction "11_11") (pintype "passive"))
      (node (ref "JP3") (pin "1") (pinfunction "1_1") (pintype "passive"))
    )
    (net (code "157") (name "unconnected-(IC1-NC-Pad8)") (class "Default")
      (node (ref "IC1") (pin "8") (pinfunction "NC_8") (pintype "input"))
    )
    (net (code "158") (name "unconnected-(IC1-NC_2-Pad1)") (class "Default")
      (node (ref "IC1") (pin "1") (pinfunction "NC_2_1") (pintype "input"))
    )
    (net (code "159") (name "unconnected-(IC2-NC-Pad8)") (class "Default")
      (node (ref "IC2") (pin "8") (pinfunction "NC_8") (pintype "input"))
    )
    (net (code "160") (name "unconnected-(IC2-NC_2-Pad1)") (class "Default")
      (node (ref "IC2") (pin "1") (pinfunction "NC_2_1") (pintype "input"))
    )
    (net (code "161") (name "unconnected-(IC3-NC-Pad8)") (class "Default")
      (node (ref "IC3") (pin "8") (pinfunction "NC_8") (pintype "input"))
    )
    (net (code "162") (name "unconnected-(IC3-NC_2-Pad1)") (class "Default")
      (node (ref "IC3") (pin "1") (pinfunction "NC_2_1") (pintype "input"))
    )
    (net (code "163") (name "unconnected-(IC4-NC-Pad8)") (class "Default")
      (node (ref "IC4") (pin "8") (pinfunction "NC_8") (pintype "input"))
    )
    (net (code "164") (name "unconnected-(IC4-NC_2-Pad1)") (class "Default")
      (node (ref "IC4") (pin "1") (pinfunction "NC_2_1") (pintype "input"))
    )
    (net (code "165") (name "unconnected-(IC14-STATUS1-Pad2)") (class "Default")
      (node (ref "IC14") (pin "2") (pinfunction "STATUS1_2") (pintype "bidirectional"))
    )
    (net (code "166") (name "unconnected-(IC14-STATUS2-Pad4)") (class "Default")
      (node (ref "IC14") (pin "4") (pinfunction "STATUS2_4") (pintype "bidirectional"))
    )
    (net (code "167") (name "unconnected-(IC15-I{slash}O-Pad6)") (class "Default")
      (node (ref "IC15") (pin "6") (pinfunction "I/O_6") (pintype "bidirectional"))
    )
    (net (code "168") (name "unconnected-(IC15-I{slash}O_4-Pad4)") (class "Default")
      (node (ref "IC15") (pin "4") (pinfunction "I/O_4_4") (pintype "bidirectional"))
    )
    (net (code "169") (name "unconnected-(J1-Pad4)") (class "Default")
      (node (ref "J1") (pin "4") (pinfunction "4_4") (pintype "passive"))
    )
    (net (code "170") (name "unconnected-(J1-Pad19)") (class "Default")
      (node (ref "J1") (pin "19") (pinfunction "19_19") (pintype "passive"))
    )
    (net (code "171") (name "unconnected-(J1-Pad20)") (class "Default")
      (node (ref "J1") (pin "20") (pinfunction "20_20") (pintype "passive"))
    )
    (net (code "172") (name "unconnected-(J1-Pad21)") (class "Default")
      (node (ref "J1") (pin "21") (pinfunction "21_21") (pintype "passive"))
    )
    (net (code "173") (name "unconnected-(J1-Pad22)") (class "Default")
      (node (ref "J1") (pin "22") (pinfunction "22_22") (pintype "passive"))
    )
    (net (code "174") (name "unconnected-(J1-Pad23)") (class "Default")
      (node (ref "J1") (pin "23") (pinfunction "23_23") (pintype "passive"))
    )
    (net (code "175") (name "unconnected-(J1-Pad44)") (class "Default")
      (node (ref "J1") (pin "44") (pinfunction "44_44") (pintype "passive"))
    )
    (net (code "176") (name "unconnected-(J1-Pad50)") (class "Default")
      (node (ref "J1") (pin "50") (pinfunction "50_50") (pintype "passive"))
    )
    (net (code "177") (name "unconnected-(J1-Pad51)") (class "Default")
      (node (ref "J1") (pin "51") (pinfunction "51_51") (pintype "passive"))
    )
    (net (code "178") (name "unconnected-(J1-Pad52)") (class "Default")
      (node (ref "J1") (pin "52") (pinfunction "52_52") (pintype "passive"))
    )
    (net (code "179") (name "unconnected-(PS1-NC-Pad1)") (class "Default")
      (node (ref "PS1") (pin "1") (pinfunction "NC_1") (pintype "no_connect"))
    )
    (net (code "180") (name "unconnected-(PS1-NC-Pad5)") (class "Default")
      (node (ref "PS1") (pin "5") (pinfunction "NC_5") (pintype "no_connect"))
    )
    (net (code "181") (name "unconnected-(PS1-NC-Pad6)") (class "Default")
      (node (ref "PS1") (pin "6") (pinfunction "NC_6") (pintype "no_connect"))
    )
    (net (code "182") (name "unconnected-(U$1-A21{slash}DAC0-Pad21{slash}DAC0)") (class "Default")
      (node (ref "U$1") (pin "21/DAC0") (pinfunction "A21/DAC0_21/DAC0") (pintype "bidirectional"))
    )
    (net (code "183") (name "unconnected-(U$1-Pad3V3)") (class "Default")
      (node (ref "U$1") (pin "3V3") (pinfunction "3V3_3V3") (pintype "bidirectional"))
    )
    (net (code "184") (name "unconnected-(U$1-Pad3V3_2)") (class "Default")
      (node (ref "U$1") (pin "3V3_2") (pinfunction "3V3_2_3V3_2") (pintype "bidirectional"))
    )
    (net (code "185") (name "unconnected-(U$1-PadA11)") (class "Default")
      (node (ref "U$1") (pin "A11") (pinfunction "A11_A11") (pintype "bidirectional"))
    )
    (net (code "186") (name "unconnected-(U$1-PadAGND)") (class "Default")
      (node (ref "U$1") (pin "AGND") (pinfunction "AGND_AGND") (pintype "bidirectional"))
    )
    (net (code "187") (name "unconnected-(U$1-PadAREF)") (class "Default")
      (node (ref "U$1") (pin "AREF") (pinfunction "AREF_AREF") (pintype "bidirectional"))
    )
    (net (code "188") (name "unconnected-(U$1-PadPROG)") (class "Default")
      (node (ref "U$1") (pin "PROG") (pinfunction "PROG_PROG") (pintype "bidirectional"))
    )
    (net (code "189") (name "unconnected-(U$1-PadU5V)") (class "Default")
      (node (ref "U$1") (pin "U5V") (pinfunction "U5V_U5V") (pintype "bidirectional"))
    )
    (net (code "190") (name "unconnected-(U$1-PadUD+)") (class "Default")
      (node (ref "U$1") (pin "UD+") (pinfunction "UD+_UD+") (pintype "bidirectional"))
    )
    (net (code "191") (name "unconnected-(U$1-PadUD-)") (class "Default")
      (node (ref "U$1") (pin "UD-") (pinfunction "UD-_UD-") (pintype "bidirectional"))
    )
    (net (code "192") (name "unconnected-(U$1-PadUGND1)") (class "Default")
      (node (ref "U$1") (pin "UGND1") (pinfunction "UGND1_UGND1") (pintype "bidirectional"))
    )
    (net (code "193") (name "unconnected-(U$1-PadUGND2)") (class "Default")
      (node (ref "U$1") (pin "UGND2") (pinfunction "UGND2_UGND2") (pintype "bidirectional"))
    )
    (net (code "194") (name "unconnected-(U$1-PadVBAT)") (class "Default")
      (node (ref "U$1") (pin "VBAT") (pinfunction "VBAT_VBAT") (pintype "bidirectional"))
    )
    (net (code "195") (name "unconnected-(U$1-PadVUSB)") (class "Default")
      (node (ref "U$1") (pin "VUSB") (pinfunction "VUSB_VUSB") (pintype "bidirectional"))
    )
    (net (code "196") (name "unconnected-(U$3-PadM0)") (class "Default")
      (node (ref "U$3") (pin "M0") (pinfunction "M0_M0") (pintype "bidirectional"))
    )
    (net (code "197") (name "unconnected-(U$3-PadM1)") (class "Default")
      (node (ref "U$3") (pin "M1") (pinfunction "M1_M1") (pintype "bidirectional"))
    )
    (net (code "198") (name "unconnected-(U$3-PadM2)") (class "Default")
      (node (ref "U$3") (pin "M2") (pinfunction "M2_M2") (pintype "bidirectional"))
    )
    (net (code "199") (name "unconnected-(U1-VREF-Pad5)") (class "Default")
      (node (ref "U1") (pin "5") (pinfunction "VREF_5") (pintype "output"))
    )
  )
)
